# TPadTabletBattery.net
KiCad netlist of a schematic drawn in EAGLE
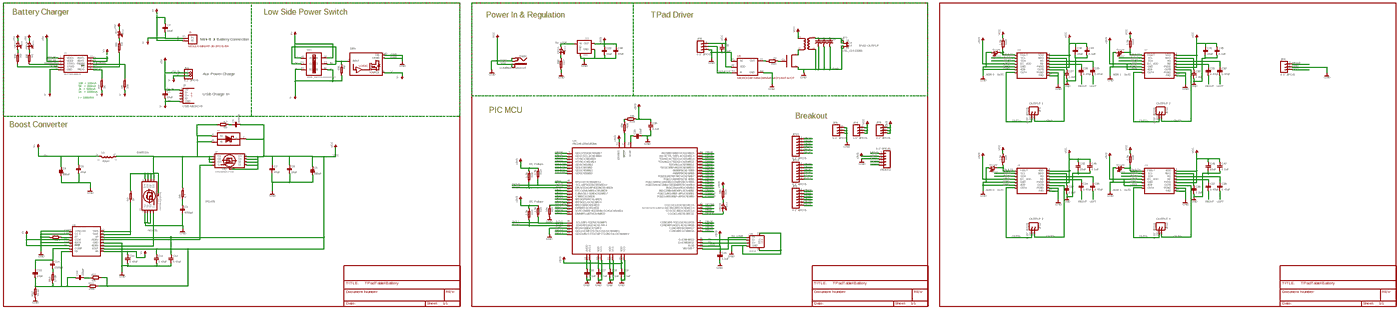
[diagram p0: schematic, sheet 1, overview]
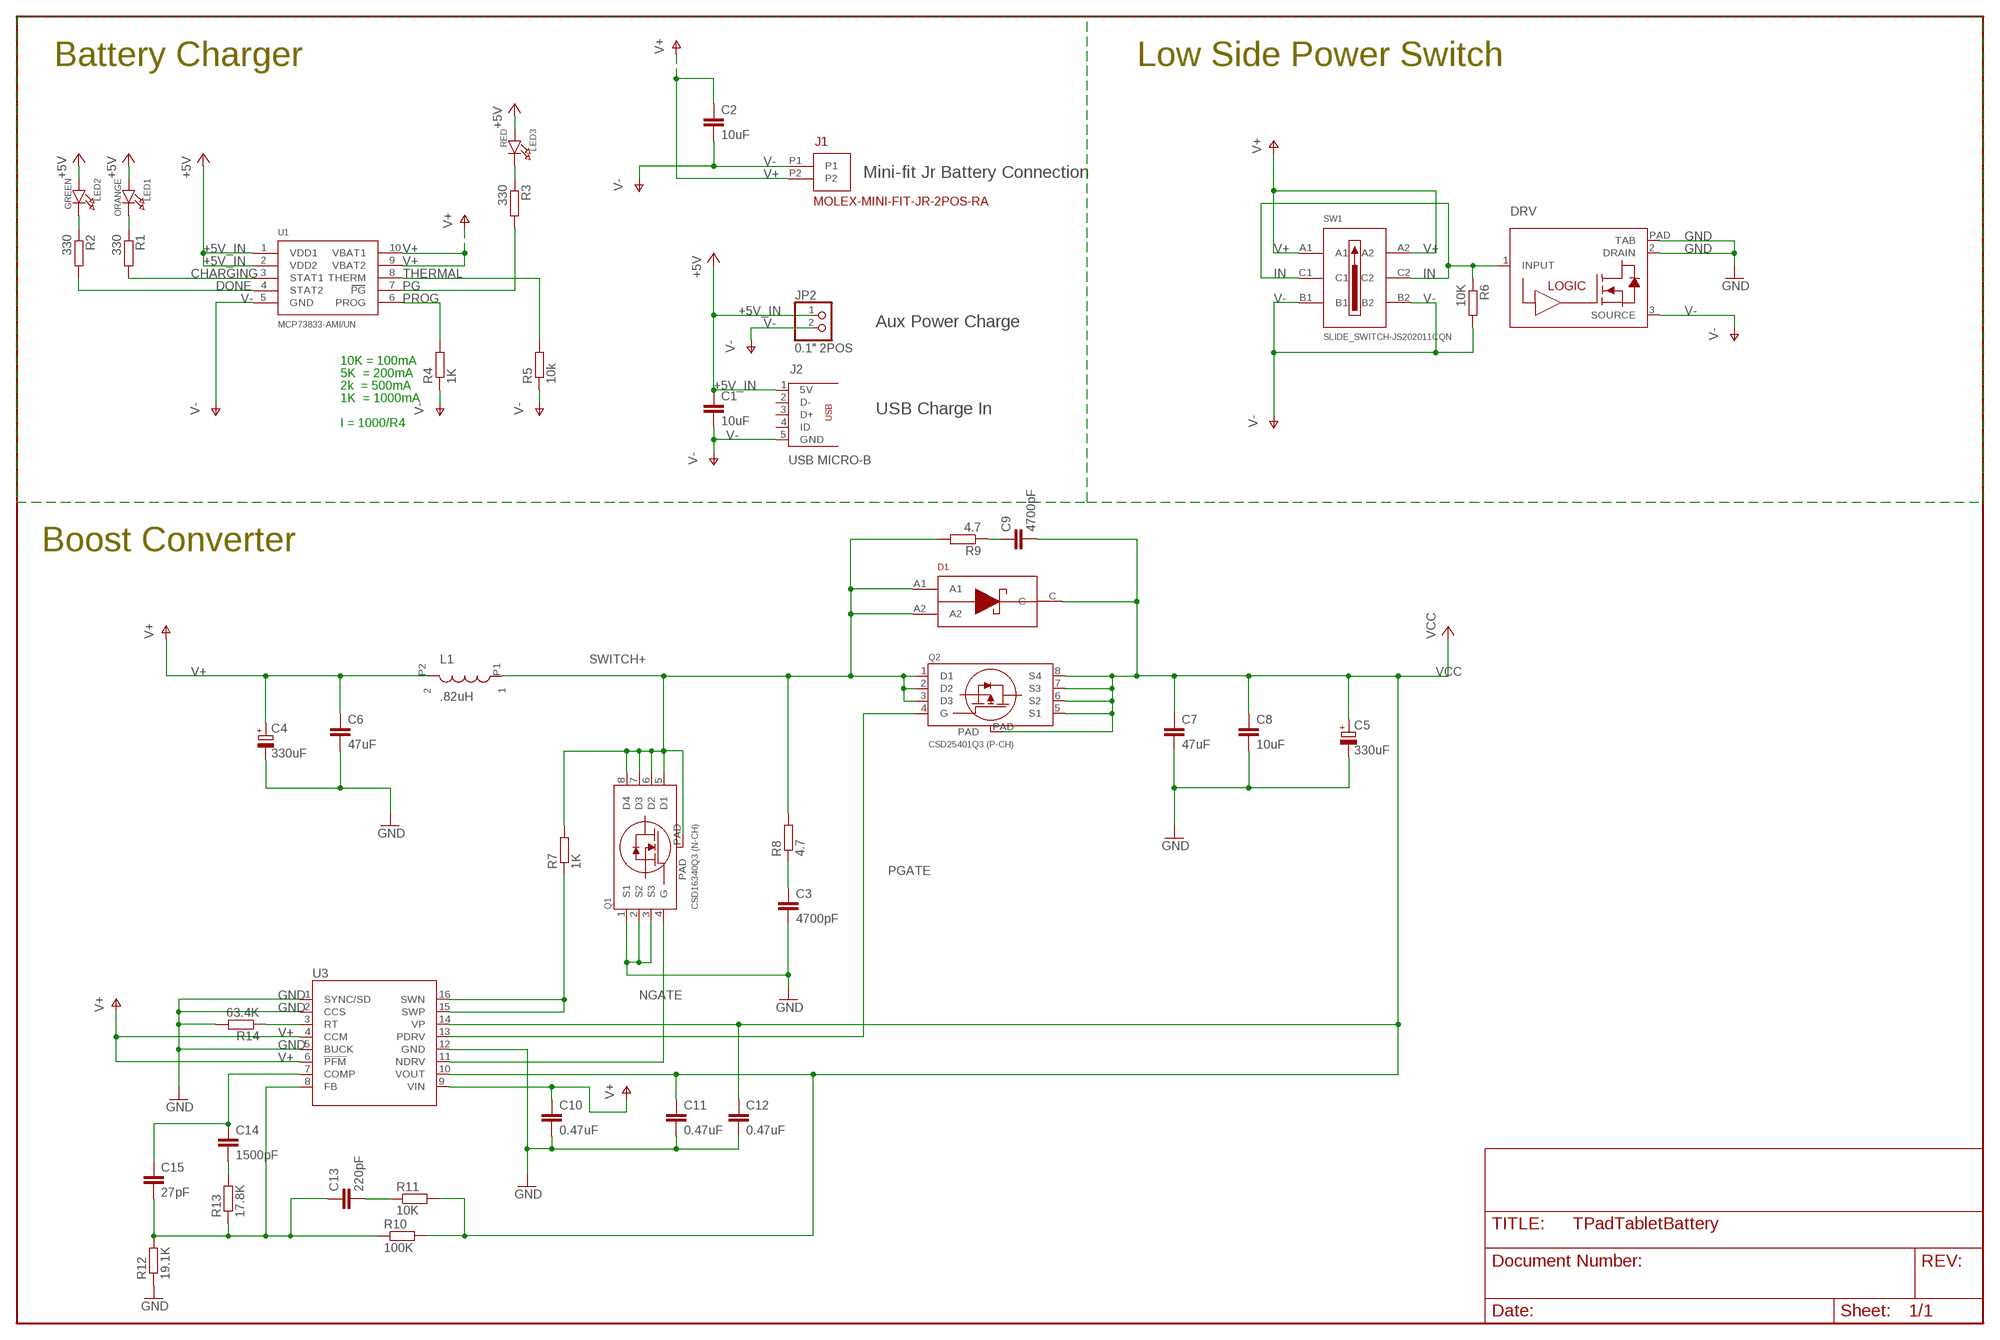
[diagram p1: schematic, sheet 1, part 1 of 4]
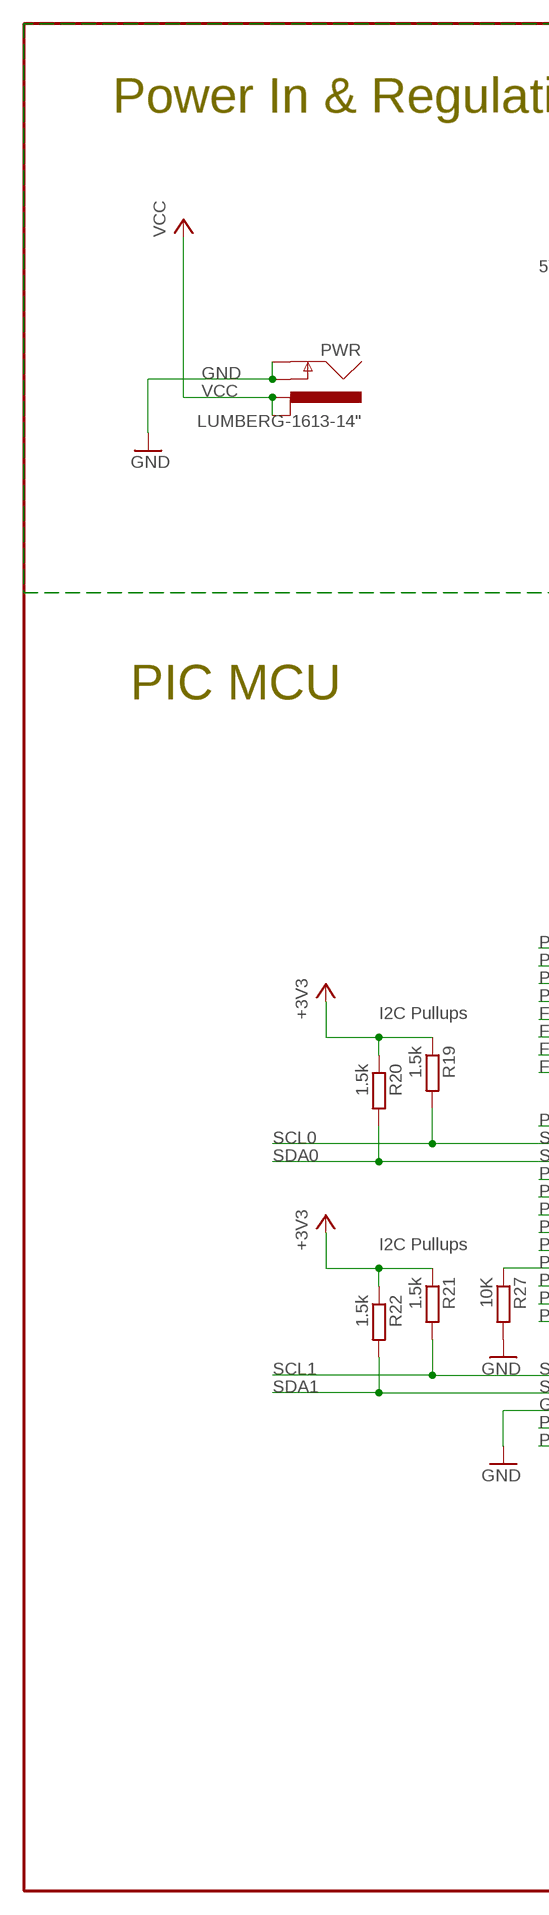
[diagram p2: schematic, sheet 1, part 2 of 4]
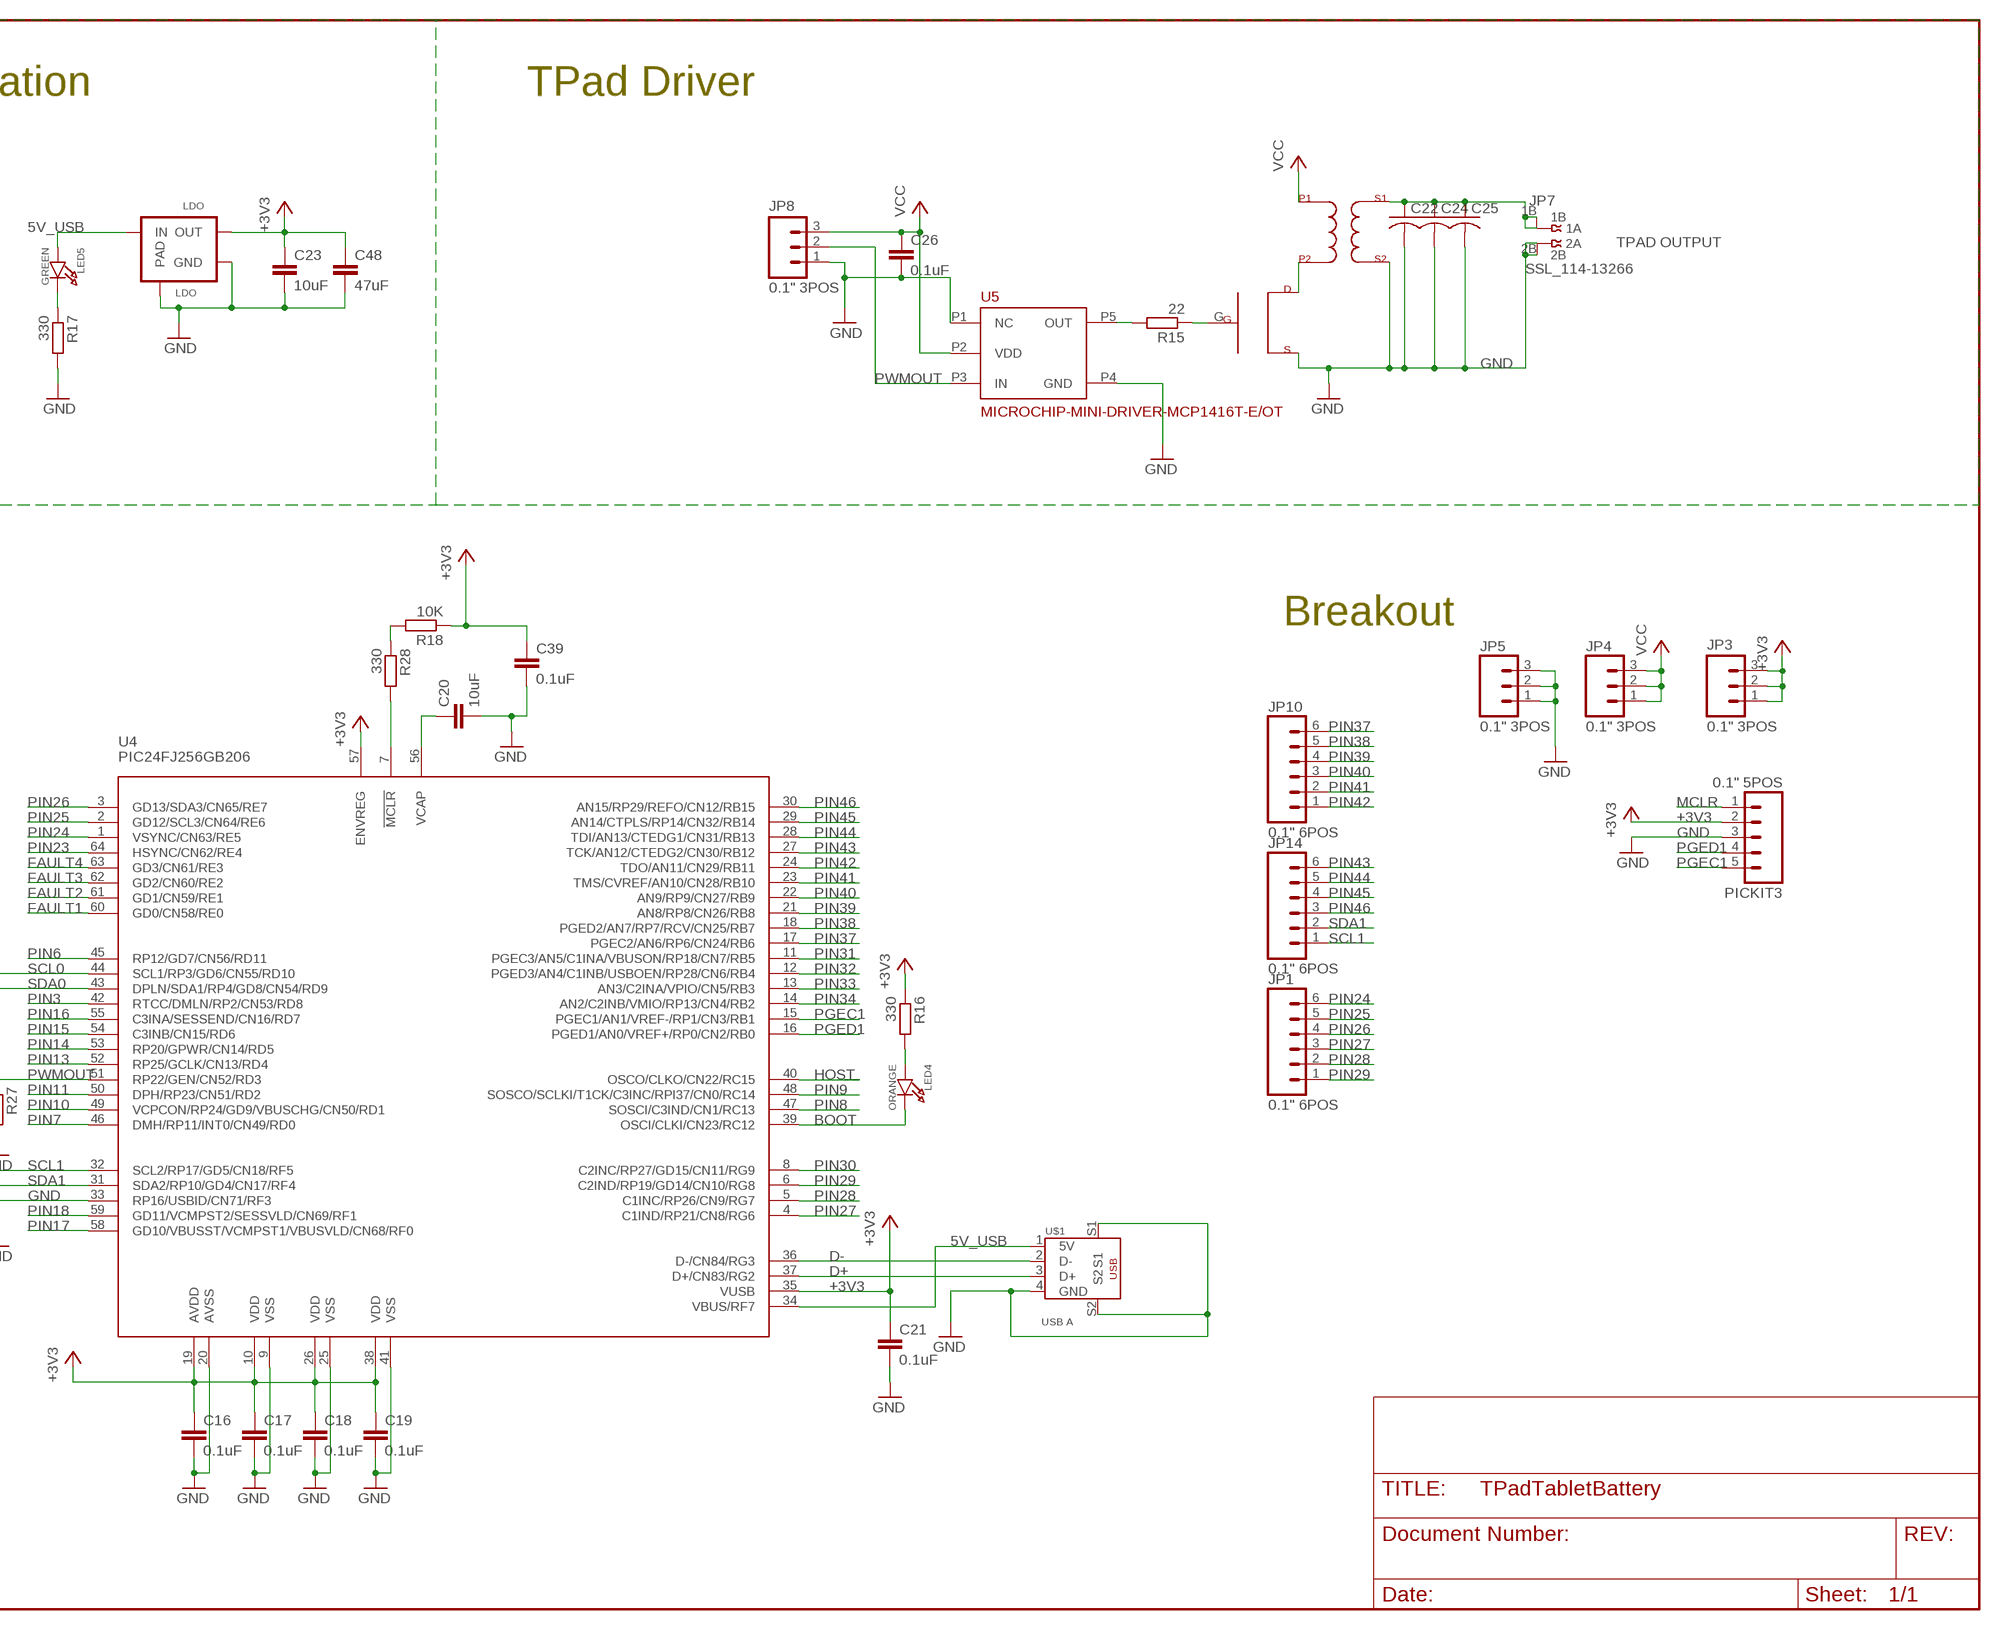
[diagram p3: schematic, sheet 1, part 3 of 4]
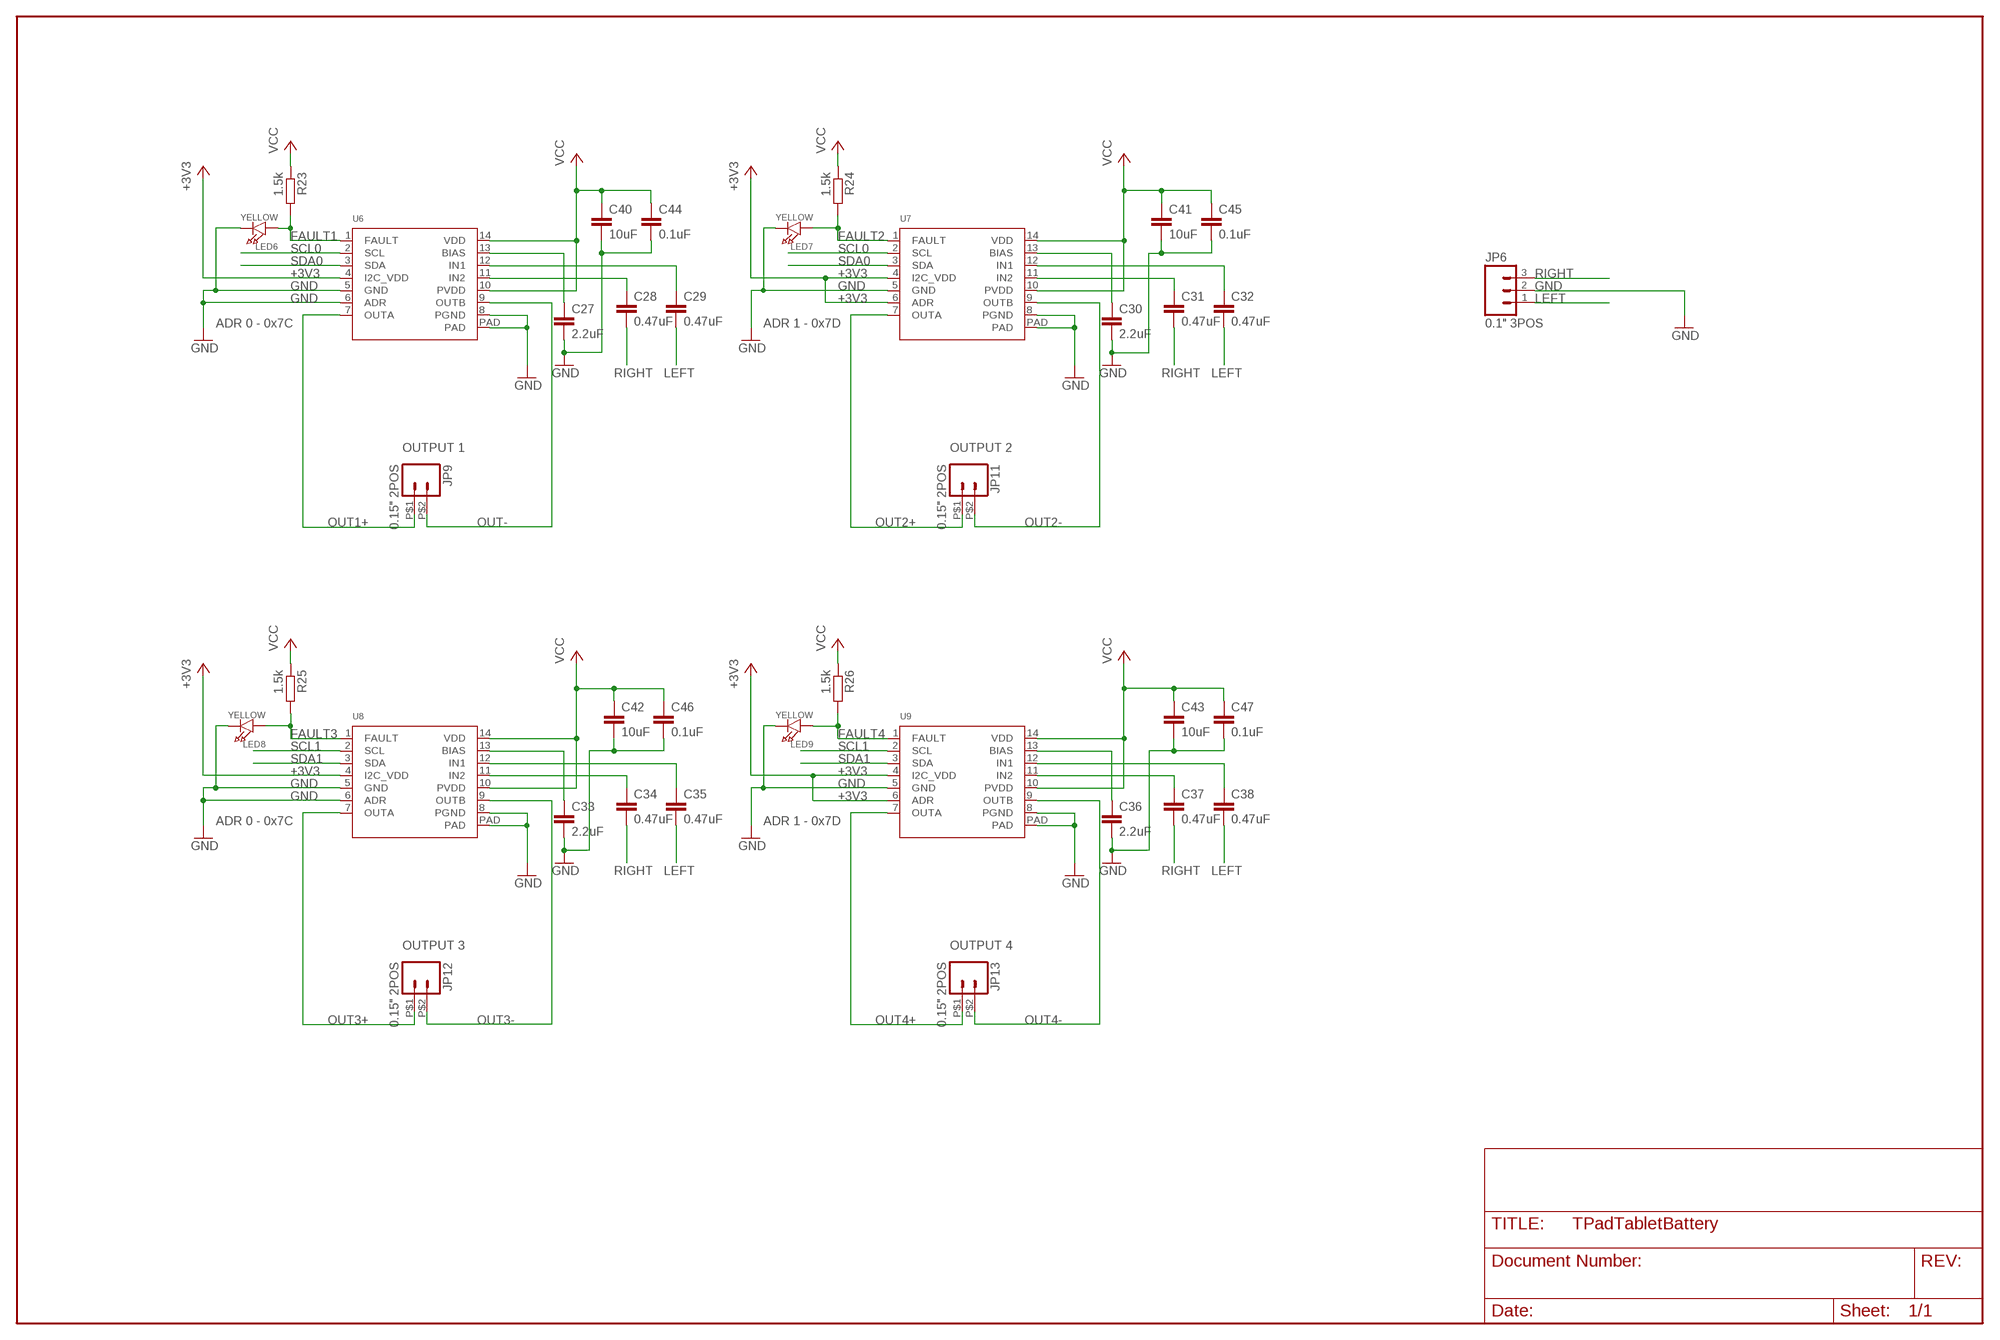
[diagram p4: schematic, sheet 1, part 4 of 4]

(export (version "E")
  (design (tool "Eeschema 10.0.6"))
  (components
    (comp (ref "C1")
      (value "10uF")
      (footprint "eagle-import:C0805")
      (libsource (lib "eagle-import") (part "C-EUC0805"))
    )
    (comp (ref "C2")
      (value "10uF")
      (footprint "eagle-import:C0805")
      (libsource (lib "eagle-import") (part "C-EUC0805"))
    )
    (comp (ref "C3")
      (value "4700pF")
      (footprint "eagle-import:C0603")
      (libsource (lib "eagle-import") (part "C-EUC0603"))
    )
    (comp (ref "C4")
      (value "330uF")
      (footprint "eagle-import:C_6032-28R")
      (libsource (lib "eagle-import") (part "CPOL-EUC/6032-28R"))
    )
    (comp (ref "C5")
      (value "330uF")
      (footprint "eagle-import:C_6032-28R")
      (libsource (lib "eagle-import") (part "CPOL-EUC/6032-28R"))
    )
    (comp (ref "C6")
      (value "47uF")
      (footprint "eagle-import:C1210")
      (libsource (lib "eagle-import") (part "C-EUC1210"))
    )
    (comp (ref "C7")
      (value "47uF")
      (footprint "eagle-import:C1210")
      (libsource (lib "eagle-import") (part "C-EUC1210"))
    )
    (comp (ref "C8")
      (value "10uF")
      (footprint "eagle-import:C0805")
      (libsource (lib "eagle-import") (part "C-EUC0805"))
    )
    (comp (ref "C9")
      (value "4700pF")
      (footprint "eagle-import:C0603")
      (libsource (lib "eagle-import") (part "C-EUC0603"))
    )
    (comp (ref "C10")
      (value "0.47uF")
      (footprint "eagle-import:C0603")
      (libsource (lib "eagle-import") (part "C-EUC0603"))
    )
    (comp (ref "C11")
      (value "0.47uF")
      (footprint "eagle-import:C0603")
      (libsource (lib "eagle-import") (part "C-EUC0603"))
    )
    (comp (ref "C12")
      (value "0.47uF")
      (footprint "eagle-import:C0603")
      (libsource (lib "eagle-import") (part "C-EUC0603"))
    )
    (comp (ref "C13")
      (value "220pF")
      (footprint "eagle-import:C0603")
      (libsource (lib "eagle-import") (part "C-EUC0603"))
    )
    (comp (ref "C14")
      (value "1500pF")
      (footprint "eagle-import:C0603")
      (libsource (lib "eagle-import") (part "C-EUC0603"))
    )
    (comp (ref "C15")
      (value "27pF")
      (footprint "eagle-import:C0603")
      (libsource (lib "eagle-import") (part "C-EUC0603"))
    )
    (comp (ref "C16")
      (value "0.1uF")
      (footprint "eagle-import:C0603")
      (libsource (lib "eagle-import") (part "C-EUC0603"))
    )
    (comp (ref "C17")
      (value "0.1uF")
      (footprint "eagle-import:C0603")
      (libsource (lib "eagle-import") (part "C-EUC0603"))
    )
    (comp (ref "C18")
      (value "0.1uF")
      (footprint "eagle-import:C0603")
      (libsource (lib "eagle-import") (part "C-EUC0603"))
    )
    (comp (ref "C19")
      (value "0.1uF")
      (footprint "eagle-import:C0603")
      (libsource (lib "eagle-import") (part "C-EUC0603"))
    )
    (comp (ref "C20")
      (value "10uF")
      (footprint "eagle-import:C0805")
      (libsource (lib "eagle-import") (part "C-EUC0805"))
    )
    (comp (ref "C21")
      (value "0.1uF")
      (footprint "eagle-import:C0603")
      (libsource (lib "eagle-import") (part "C-EUC0603"))
    )
    (comp (ref "C22")
      (value "C-US050-035X075")
      (footprint "eagle-import:C050-035X075")
      (libsource (lib "eagle-import") (part "C-US050-035X075"))
    )
    (comp (ref "C23")
      (value "10uF")
      (footprint "eagle-import:C0805")
      (libsource (lib "eagle-import") (part "C-EUC0805"))
    )
    (comp (ref "C24")
      (value "C-US050-035X075")
      (footprint "eagle-import:C050-035X075")
      (libsource (lib "eagle-import") (part "C-US050-035X075"))
    )
    (comp (ref "C25")
      (value "C-US050-035X075")
      (footprint "eagle-import:C050-035X075")
      (libsource (lib "eagle-import") (part "C-US050-035X075"))
    )
    (comp (ref "C26")
      (value "0.1uF")
      (footprint "eagle-import:C0603")
      (libsource (lib "eagle-import") (part "C-EUC0603"))
    )
    (comp (ref "C27")
      (value "2.2uF")
      (footprint "eagle-import:C0603")
      (libsource (lib "eagle-import") (part "C-EUC0603"))
    )
    (comp (ref "C28")
      (value "0.47uF")
      (footprint "eagle-import:C0603")
      (libsource (lib "eagle-import") (part "C-EUC0603"))
    )
    (comp (ref "C29")
      (value "0.47uF")
      (footprint "eagle-import:C0603")
      (libsource (lib "eagle-import") (part "C-EUC0603"))
    )
    (comp (ref "C30")
      (value "2.2uF")
      (footprint "eagle-import:C0603")
      (libsource (lib "eagle-import") (part "C-EUC0603"))
    )
    (comp (ref "C31")
      (value "0.47uF")
      (footprint "eagle-import:C0603")
      (libsource (lib "eagle-import") (part "C-EUC0603"))
    )
    (comp (ref "C32")
      (value "0.47uF")
      (footprint "eagle-import:C0603")
      (libsource (lib "eagle-import") (part "C-EUC0603"))
    )
    (comp (ref "C33")
      (value "2.2uF")
      (footprint "eagle-import:C0603")
      (libsource (lib "eagle-import") (part "C-EUC0603"))
    )
    (comp (ref "C34")
      (value "0.47uF")
      (footprint "eagle-import:C0603")
      (libsource (lib "eagle-import") (part "C-EUC0603"))
    )
    (comp (ref "C35")
      (value "0.47uF")
      (footprint "eagle-import:C0603")
      (libsource (lib "eagle-import") (part "C-EUC0603"))
    )
    (comp (ref "C36")
      (value "2.2uF")
      (footprint "eagle-import:C0603")
      (libsource (lib "eagle-import") (part "C-EUC0603"))
    )
    (comp (ref "C37")
      (value "0.47uF")
      (footprint "eagle-import:C0603")
      (libsource (lib "eagle-import") (part "C-EUC0603"))
    )
    (comp (ref "C38")
      (value "0.47uF")
      (footprint "eagle-import:C0603")
      (libsource (lib "eagle-import") (part "C-EUC0603"))
    )
    (comp (ref "C39")
      (value "0.1uF")
      (footprint "eagle-import:C0603")
      (libsource (lib "eagle-import") (part "C-EUC0603"))
    )
    (comp (ref "C40")
      (value "10uF")
      (footprint "eagle-import:C0805")
      (libsource (lib "eagle-import") (part "C-EUC0805"))
    )
    (comp (ref "C41")
      (value "10uF")
      (footprint "eagle-import:C0805")
      (libsource (lib "eagle-import") (part "C-EUC0805"))
    )
    (comp (ref "C42")
      (value "10uF")
      (footprint "eagle-import:C0805")
      (libsource (lib "eagle-import") (part "C-EUC0805"))
    )
    (comp (ref "C43")
      (value "10uF")
      (footprint "eagle-import:C0805")
      (libsource (lib "eagle-import") (part "C-EUC0805"))
    )
    (comp (ref "C44")
      (value "0.1uF")
      (footprint "eagle-import:C0603")
      (libsource (lib "eagle-import") (part "C-EUC0603"))
    )
    (comp (ref "C45")
      (value "0.1uF")
      (footprint "eagle-import:C0603")
      (libsource (lib "eagle-import") (part "C-EUC0603"))
    )
    (comp (ref "C46")
      (value "0.1uF")
      (footprint "eagle-import:C0603")
      (libsource (lib "eagle-import") (part "C-EUC0603"))
    )
    (comp (ref "C47")
      (value "0.1uF")
      (footprint "eagle-import:C0603")
      (libsource (lib "eagle-import") (part "C-EUC0603"))
    )
    (comp (ref "C48")
      (value "47uF")
      (footprint "eagle-import:C1210")
      (libsource (lib "eagle-import") (part "C-EUC1210"))
    )
    (comp (ref "D1")
      (value "POWER-DIODE_PDS835L")
      (footprint "eagle-import:POWER-DIODE_PDS835L")
      (libsource (lib "eagle-import") (part "POWER-DIODE_PDS835L"))
    )
    (comp (ref "DRV")
      (value "VLN5050")
      (footprint "eagle-import:SOT-223")
      (libsource (lib "eagle-import") (part "VLN5050"))
    )
    (comp (ref "J1")
      (value "MOLEX-MINI-FIT-JR-2POS-RA")
      (footprint "eagle-import:MOLEX-MINI-FIT-JR-2POS-RA")
      (libsource (lib "eagle-import") (part "MOLEX-MINI-FIT-JR-2POS-RA"))
    )
    (comp (ref "J2")
      (value "USB MICRO-B")
      (footprint "eagle-import:USB-MICROB_SMD")
      (libsource (lib "eagle-import") (part "USB_MICROMICRO-BAMPHENOL_10118193-0001LF"))
    )
    (comp (ref "JP1")
      (value "0.1\" 6POS")
      (footprint "eagle-import:1X06")
      (libsource (lib "eagle-import") (part "M06SIP"))
    )
    (comp (ref "JP2")
      (value "0.1\" 2POS")
      (footprint "eagle-import:MICROBUILDER_1X02_ROUND")
      (libsource (lib "eagle-import") (part "MICROBUILDER_HEADER-1X2ROUND"))
    )
    (comp (ref "JP3")
      (value "0.1\" 3POS")
      (footprint "eagle-import:1X03")
      (libsource (lib "eagle-import") (part "M03PTH"))
    )
    (comp (ref "JP4")
      (value "0.1\" 3POS")
      (footprint "eagle-import:1X03")
      (libsource (lib "eagle-import") (part "M03PTH"))
    )
    (comp (ref "JP5")
      (value "0.1\" 3POS")
      (footprint "eagle-import:1X03")
      (libsource (lib "eagle-import") (part "M03PTH"))
    )
    (comp (ref "JP6")
      (value "0.1\" 3POS")
      (footprint "eagle-import:1X03")
      (libsource (lib "eagle-import") (part "M03PTH"))
    )
    (comp (ref "JP7")
      (value "SSL_114-13266")
      (footprint "eagle-import:SSL_114-13266")
      (libsource (lib "eagle-import") (part "SSL_114-13266"))
    )
    (comp (ref "JP8")
      (value "0.1\" 3POS")
      (footprint "eagle-import:1X03")
      (libsource (lib "eagle-import") (part "M03PTH"))
    )
    (comp (ref "JP9")
      (value "0.15\" 2POS")
      (footprint "eagle-import:1X02_BIG")
      (libsource (lib "eagle-import") (part "M02PTH2"))
    )
    (comp (ref "JP10")
      (value "0.1\" 6POS")
      (footprint "eagle-import:1X06")
      (libsource (lib "eagle-import") (part "M06SIP"))
    )
    (comp (ref "JP11")
      (value "0.15\" 2POS")
      (footprint "eagle-import:1X02_BIG")
      (libsource (lib "eagle-import") (part "M02PTH2"))
    )
    (comp (ref "JP12")
      (value "0.15\" 2POS")
      (footprint "eagle-import:1X02_BIG")
      (libsource (lib "eagle-import") (part "M02PTH2"))
    )
    (comp (ref "JP13")
      (value "0.15\" 2POS")
      (footprint "eagle-import:1X02_BIG")
      (libsource (lib "eagle-import") (part "M02PTH2"))
    )
    (comp (ref "JP14")
      (value "0.1\" 6POS")
      (footprint "eagle-import:1X06")
      (libsource (lib "eagle-import") (part "M06SIP"))
    )
    (comp (ref "L1")
      (value ".82uH")
      (footprint "eagle-import:.82UH_INDUCTOR-IHLP3232DZERR82M01")
      (libsource (lib "eagle-import") (part ".82UH_INDUCTOR-IHLP3232DZERR82M01"))
    )
    (comp (ref "LDO")
      (value "LDO")
      (footprint "eagle-import:SOT-223")
      (libsource (lib "eagle-import") (part "LDO"))
    )
    (comp (ref "LED1")
      (value "ORANGE")
      (footprint "eagle-import:MICROBUILDER_CHIPLED_0603")
      (libsource (lib "eagle-import") (part "MICROBUILDER_LED0603"))
    )
    (comp (ref "LED2")
      (value "GREEN")
      (footprint "eagle-import:MICROBUILDER_CHIPLED_0603")
      (libsource (lib "eagle-import") (part "MICROBUILDER_LED0603"))
    )
    (comp (ref "LED3")
      (value "RED")
      (footprint "eagle-import:MICROBUILDER_CHIPLED_0603")
      (libsource (lib "eagle-import") (part "MICROBUILDER_LED0603"))
    )
    (comp (ref "LED4")
      (value "ORANGE")
      (footprint "eagle-import:MICROBUILDER_CHIPLED_0603")
      (libsource (lib "eagle-import") (part "MICROBUILDER_LED0603"))
    )
    (comp (ref "LED5")
      (value "GREEN")
      (footprint "eagle-import:MICROBUILDER_CHIPLED_0603")
      (libsource (lib "eagle-import") (part "MICROBUILDER_LED0603"))
    )
    (comp (ref "LED6")
      (value "YELLOW")
      (footprint "eagle-import:MICROBUILDER_CHIPLED_0603")
      (libsource (lib "eagle-import") (part "MICROBUILDER_LED0603"))
    )
    (comp (ref "LED7")
      (value "YELLOW")
      (footprint "eagle-import:MICROBUILDER_CHIPLED_0603")
      (libsource (lib "eagle-import") (part "MICROBUILDER_LED0603"))
    )
    (comp (ref "LED8")
      (value "YELLOW")
      (footprint "eagle-import:MICROBUILDER_CHIPLED_0603")
      (libsource (lib "eagle-import") (part "MICROBUILDER_LED0603"))
    )
    (comp (ref "LED9")
      (value "YELLOW")
      (footprint "eagle-import:MICROBUILDER_CHIPLED_0603")
      (libsource (lib "eagle-import") (part "MICROBUILDER_LED0603"))
    )
    (comp (ref "PICKIT3")
      (value "0.1\" 5POS")
      (footprint "eagle-import:1X05")
      (libsource (lib "eagle-import") (part "M05PTH"))
    )
    (comp (ref "PWR")
      (value "LUMBERG-1613-14\"")
      (footprint "eagle-import:LUMBERG-1613_14")
      (libsource (lib "eagle-import") (part "LUMBERG-1613-14{dblquote}"))
    )
    (comp (ref "Q1")
      (value "CSD16340Q3")
      (footprint "eagle-import:CSDXXXXQ3")
      (libsource (lib "eagle-import") (part "CSD16340Q3"))
    )
    (comp (ref "Q2")
      (value "CSD25401Q3")
      (footprint "eagle-import:CSDXXXXQ3")
      (libsource (lib "eagle-import") (part "CSD25401Q3"))
    )
    (comp (ref "Q3")
      (value "STP27N3LH5")
      (footprint "eagle-import:TPAD_TO220")
      (libsource (lib "eagle-import") (part "TPAD_IRF520N"))
    )
    (comp (ref "R1")
      (value "330")
      (footprint "eagle-import:R0603")
      (libsource (lib "eagle-import") (part "R-EU_R0603"))
    )
    (comp (ref "R2")
      (value "330")
      (footprint "eagle-import:R0603")
      (libsource (lib "eagle-import") (part "R-EU_R0603"))
    )
    (comp (ref "R3")
      (value "330")
      (footprint "eagle-import:R0603")
      (libsource (lib "eagle-import") (part "R-EU_R0603"))
    )
    (comp (ref "R4")
      (value "1K")
      (footprint "eagle-import:R0805")
      (libsource (lib "eagle-import") (part "R-EU_R0805"))
    )
    (comp (ref "R5")
      (value "10k")
      (footprint "eagle-import:R0805")
      (libsource (lib "eagle-import") (part "R-EU_R0805"))
    )
    (comp (ref "R6")
      (value "10K")
      (footprint "eagle-import:R0603")
      (libsource (lib "eagle-import") (part "R-EU_R0603"))
    )
    (comp (ref "R7")
      (value "1K")
      (footprint "eagle-import:R0603")
      (libsource (lib "eagle-import") (part "R-EU_R0603"))
    )
    (comp (ref "R8")
      (value "4.7")
      (footprint "eagle-import:R0603")
      (libsource (lib "eagle-import") (part "R-EU_R0603"))
    )
    (comp (ref "R9")
      (value "4.7")
      (footprint "eagle-import:R0603")
      (libsource (lib "eagle-import") (part "R-EU_R0603"))
    )
    (comp (ref "R10")
      (value "100K")
      (footprint "eagle-import:R0603")
      (libsource (lib "eagle-import") (part "R-EU_R0603"))
    )
    (comp (ref "R11")
      (value "10K")
      (footprint "eagle-import:R0603")
      (libsource (lib "eagle-import") (part "R-EU_R0603"))
    )
    (comp (ref "R12")
      (value "19.1K")
      (footprint "eagle-import:R0603")
      (libsource (lib "eagle-import") (part "R-EU_R0603"))
    )
    (comp (ref "R13")
      (value "17.8K")
      (footprint "eagle-import:R0603")
      (libsource (lib "eagle-import") (part "R-EU_R0603"))
    )
    (comp (ref "R14")
      (value "63.4K")
      (footprint "eagle-import:R0603")
      (libsource (lib "eagle-import") (part "R-EU_R0603"))
    )
    (comp (ref "R15")
      (value "22")
      (footprint "eagle-import:R0603")
      (libsource (lib "eagle-import") (part "R-EU_R0603"))
    )
    (comp (ref "R16")
      (value "330")
      (footprint "eagle-import:R0603")
      (libsource (lib "eagle-import") (part "R-EU_R0603"))
    )
    (comp (ref "R17")
      (value "330")
      (footprint "eagle-import:R0603")
      (libsource (lib "eagle-import") (part "R-EU_R0603"))
    )
    (comp (ref "R18")
      (value "10K")
      (footprint "eagle-import:R0603")
      (libsource (lib "eagle-import") (part "R-EU_R0603"))
    )
    (comp (ref "R19")
      (value "1.5k")
      (footprint "eagle-import:R0603")
      (libsource (lib "eagle-import") (part "R-EU_R0603"))
    )
    (comp (ref "R20")
      (value "1.5k")
      (footprint "eagle-import:R0603")
      (libsource (lib "eagle-import") (part "R-EU_R0603"))
    )
    (comp (ref "R21")
      (value "1.5k")
      (footprint "eagle-import:R0603")
      (libsource (lib "eagle-import") (part "R-EU_R0603"))
    )
    (comp (ref "R22")
      (value "1.5k")
      (footprint "eagle-import:R0603")
      (libsource (lib "eagle-import") (part "R-EU_R0603"))
    )
    (comp (ref "R23")
      (value "1.5k")
      (footprint "eagle-import:R0603")
      (libsource (lib "eagle-import") (part "R-EU_R0603"))
    )
    (comp (ref "R24")
      (value "1.5k")
      (footprint "eagle-import:R0603")
      (libsource (lib "eagle-import") (part "R-EU_R0603"))
    )
    (comp (ref "R25")
      (value "1.5k")
      (footprint "eagle-import:R0603")
      (libsource (lib "eagle-import") (part "R-EU_R0603"))
    )
    (comp (ref "R26")
      (value "1.5k")
      (footprint "eagle-import:R0603")
      (libsource (lib "eagle-import") (part "R-EU_R0603"))
    )
    (comp (ref "R27")
      (value "10K")
      (footprint "eagle-import:R0603")
      (libsource (lib "eagle-import") (part "R-EU_R0603"))
    )
    (comp (ref "R28")
      (value "330")
      (footprint "eagle-import:R0603")
      (libsource (lib "eagle-import") (part "R-EU_R0603"))
    )
    (comp (ref "SW1")
      (value "SLIDE_SWITCH-JS202011CQN")
      (footprint "eagle-import:SLIDE_SWITCH-JS202011CQN")
      (libsource (lib "eagle-import") (part "SLIDE_SWITCH-JS202011CQN"))
    )
    (comp (ref "U$1")
      (value "USB A")
      (footprint "eagle-import:USB-A_SOCKET-THT")
      (libsource (lib "eagle-import") (part "USBSOCKET-THT"))
    )
    (comp (ref "U$4")
      (value "TRANSFORMER")
      (footprint "eagle-import:TRANSFORMER")
      (libsource (lib "eagle-import") (part "TRANSFORMER"))
    )
    (comp (ref "U1")
      (value "MCP73833-AMI/UN")
      (footprint "eagle-import:MICROBUILDER_MSOP10")
      (libsource (lib "eagle-import") (part "MICROBUILDER_MCP73833"))
    )
    (comp (ref "U3")
      (value "TPS43000")
      (footprint "eagle-import:TSSOP16")
      (libsource (lib "eagle-import") (part "TPS43000"))
    )
    (comp (ref "U4")
      (value "PIC24FJ256GB206")
      (footprint "eagle-import:PIC24FXXX_TQFP64")
      (libsource (lib "eagle-import") (part "PIC24FXXXDAX06"))
    )
    (comp (ref "U5")
      (value "MICROCHIP-MINI-DRIVER-MCP1416T-E/OT")
      (footprint "eagle-import:MICROCHIP-MINI-DRIVER-MCP1416T-E_OT")
      (libsource (lib "eagle-import") (part "MICROCHIP-MINI-DRIVER-MCP1416T-E/OT"))
    )
    (comp (ref "U6")
      (value "LM48100Q")
      (footprint "eagle-import:LM48100")
      (libsource (lib "eagle-import") (part "LM48100Q"))
    )
    (comp (ref "U7")
      (value "LM48100Q")
      (footprint "eagle-import:LM48100")
      (libsource (lib "eagle-import") (part "LM48100Q"))
    )
    (comp (ref "U8")
      (value "LM48100Q")
      (footprint "eagle-import:LM48100")
      (libsource (lib "eagle-import") (part "LM48100Q"))
    )
    (comp (ref "U9")
      (value "LM48100Q")
      (footprint "eagle-import:LM48100")
      (libsource (lib "eagle-import") (part "LM48100Q"))
    )
  )
  (nets
    (net (code "1") (name "+3V3") (class "Default")
      (node (ref "C16") (pin "1") (pinfunction "1_1") (pintype "passive"))
      (node (ref "C17") (pin "1") (pinfunction "1_1") (pintype "passive"))
      (node (ref "C18") (pin "1") (pinfunction "1_1") (pintype "passive"))
      (node (ref "C19") (pin "1") (pinfunction "1_1") (pintype "passive"))
      (node (ref "C21") (pin "1") (pinfunction "1_1") (pintype "passive"))
      (node (ref "C23") (pin "1") (pinfunction "1_1") (pintype "passive"))
      (node (ref "C39") (pin "1") (pinfunction "1_1") (pintype "passive"))
      (node (ref "C48") (pin "1") (pinfunction "1_1") (pintype "passive"))
      (node (ref "JP3") (pin "1") (pinfunction "1_1") (pintype "passive"))
      (node (ref "JP3") (pin "2") (pinfunction "2_2") (pintype "passive"))
      (node (ref "JP3") (pin "3") (pinfunction "3_3") (pintype "passive"))
      (node (ref "LDO") (pin "3") (pinfunction "OUT_3") (pintype "passive"))
      (node (ref "PICKIT3") (pin "2") (pinfunction "2_2") (pintype "passive"))
      (node (ref "R16") (pin "1") (pinfunction "1_1") (pintype "passive"))
      (node (ref "R18") (pin "1") (pinfunction "1_1") (pintype "passive"))
      (node (ref "R19") (pin "1") (pinfunction "1_1") (pintype "passive"))
      (node (ref "R20") (pin "1") (pinfunction "1_1") (pintype "passive"))
      (node (ref "R21") (pin "1") (pinfunction "1_1") (pintype "passive"))
      (node (ref "R22") (pin "1") (pinfunction "1_1") (pintype "passive"))
      (node (ref "U4") (pin "10") (pinfunction "VDD_10") (pintype "power_in"))
      (node (ref "U4") (pin "19") (pinfunction "AVDD_19") (pintype "power_in"))
      (node (ref "U4") (pin "26") (pinfunction "VDD_26") (pintype "power_in"))
      (node (ref "U4") (pin "35") (pinfunction "VUSB_35") (pintype "power_in"))
      (node (ref "U4") (pin "38") (pinfunction "VDD_38") (pintype "power_in"))
      (node (ref "U4") (pin "57") (pinfunction "ENVREG_57") (pintype "input"))
      (node (ref "U6") (pin "4") (pinfunction "I2C_VDD_4") (pintype "bidirectional"))
      (node (ref "U7") (pin "4") (pinfunction "I2C_VDD_4") (pintype "bidirectional"))
      (node (ref "U7") (pin "6") (pinfunction "ADR_6") (pintype "bidirectional"))
      (node (ref "U8") (pin "4") (pinfunction "I2C_VDD_4") (pintype "bidirectional"))
      (node (ref "U9") (pin "4") (pinfunction "I2C_VDD_4") (pintype "bidirectional"))
      (node (ref "U9") (pin "6") (pinfunction "ADR_6") (pintype "bidirectional"))
    )
    (net (code "2") (name "+5V") (class "Default")
      (node (ref "C1") (pin "1") (pinfunction "1_1") (pintype "passive"))
      (node (ref "J2") (pin "1") (pinfunction "5V_1") (pintype "bidirectional"))
      (node (ref "JP2") (pin "1") (pinfunction "1_1") (pintype "passive"))
      (node (ref "LED1") (pin "A") (pinfunction "A_A") (pintype "passive"))
      (node (ref "LED2") (pin "A") (pinfunction "A_A") (pintype "passive"))
      (node (ref "LED3") (pin "A") (pinfunction "A_A") (pintype "passive"))
      (node (ref "U1") (pin "1") (pinfunction "VDD1_1") (pintype "bidirectional"))
      (node (ref "U1") (pin "2") (pinfunction "VDD2_2") (pintype "bidirectional"))
    )
    (net (code "3") (name "/5V_USB") (class "Default")
      (node (ref "LDO") (pin "1") (pinfunction "IN_1") (pintype "input"))
      (node (ref "LED5") (pin "A") (pinfunction "A_A") (pintype "passive"))
      (node (ref "U$1") (pin "1") (pinfunction "5V_1") (pintype "bidirectional"))
      (node (ref "U4") (pin "34") (pinfunction "VBUS/RF7_34") (pintype "input"))
    )
    (net (code "4") (name "/BOOT") (class "Default")
      (node (ref "LED4") (pin "C") (pinfunction "C_C") (pintype "passive"))
      (node (ref "U4") (pin "39") (pinfunction "OSCI/CLKI/CN23/RC12_39") (pintype "bidirectional"))
    )
    (net (code "5") (name "/CHARGING") (class "Default")
      (node (ref "R1") (pin "2") (pinfunction "2_2") (pintype "passive"))
      (node (ref "U1") (pin "3") (pinfunction "STAT1_3") (pintype "bidirectional"))
    )
    (net (code "6") (name "/D+") (class "Default")
      (node (ref "U$1") (pin "3") (pinfunction "D+_3") (pintype "bidirectional"))
      (node (ref "U4") (pin "37") (pinfunction "D+/CN83/RG2_37") (pintype "bidirectional"))
    )
    (net (code "7") (name "/D-") (class "Default")
      (node (ref "U$1") (pin "2") (pinfunction "D-_2") (pintype "bidirectional"))
      (node (ref "U4") (pin "36") (pinfunction "D-/CN84/RG3_36") (pintype "bidirectional"))
    )
    (net (code "8") (name "/DONE") (class "Default")
      (node (ref "R2") (pin "2") (pinfunction "2_2") (pintype "passive"))
      (node (ref "U1") (pin "4") (pinfunction "STAT2_4") (pintype "bidirectional"))
    )
    (net (code "9") (name "/FAULT1") (class "Default")
      (node (ref "LED6") (pin "A") (pinfunction "A_A") (pintype "passive"))
      (node (ref "R23") (pin "2") (pinfunction "2_2") (pintype "passive"))
      (node (ref "U4") (pin "60") (pinfunction "GD0/CN58/RE0_60") (pintype "bidirectional"))
      (node (ref "U6") (pin "1") (pinfunction "FAULT_1") (pintype "bidirectional"))
    )
    (net (code "10") (name "/FAULT2") (class "Default")
      (node (ref "LED7") (pin "A") (pinfunction "A_A") (pintype "passive"))
      (node (ref "R24") (pin "2") (pinfunction "2_2") (pintype "passive"))
      (node (ref "U4") (pin "61") (pinfunction "GD1/CN59/RE1_61") (pintype "bidirectional"))
      (node (ref "U7") (pin "1") (pinfunction "FAULT_1") (pintype "bidirectional"))
    )
    (net (code "11") (name "/FAULT3") (class "Default")
      (node (ref "LED8") (pin "A") (pinfunction "A_A") (pintype "passive"))
      (node (ref "R25") (pin "2") (pinfunction "2_2") (pintype "passive"))
      (node (ref "U4") (pin "62") (pinfunction "GD2/CN60/RE2_62") (pintype "bidirectional"))
      (node (ref "U8") (pin "1") (pinfunction "FAULT_1") (pintype "bidirectional"))
    )
    (net (code "12") (name "/FAULT4") (class "Default")
      (node (ref "LED9") (pin "A") (pinfunction "A_A") (pintype "passive"))
      (node (ref "R26") (pin "2") (pinfunction "2_2") (pintype "passive"))
      (node (ref "U4") (pin "63") (pinfunction "GD3/CN61/RE3_63") (pintype "bidirectional"))
      (node (ref "U9") (pin "1") (pinfunction "FAULT_1") (pintype "bidirectional"))
    )
    (net (code "13") (name "/HOST") (class "Default")
      (node (ref "U4") (pin "40") (pinfunction "OSCO/CLKO/CN22/RC15_40") (pintype "bidirectional"))
    )
    (net (code "14") (name "/IN") (class "Default")
      (node (ref "DRV") (pin "1") (pinfunction "INPUT_1") (pintype "bidirectional"))
      (node (ref "R6") (pin "1") (pinfunction "1_1") (pintype "passive"))
      (node (ref "SW1") (pin "C1") (pinfunction "C1_C1") (pintype "bidirectional"))
      (node (ref "SW1") (pin "C2") (pinfunction "C2_C2") (pintype "bidirectional"))
    )
    (net (code "15") (name "/LEFT") (class "Default")
      (node (ref "C29") (pin "2") (pinfunction "2_2") (pintype "passive"))
      (node (ref "C32") (pin "2") (pinfunction "2_2") (pintype "passive"))
      (node (ref "C35") (pin "2") (pinfunction "2_2") (pintype "passive"))
      (node (ref "C38") (pin "2") (pinfunction "2_2") (pintype "passive"))
      (node (ref "JP6") (pin "1") (pinfunction "1_1") (pintype "passive"))
    )
    (net (code "16") (name "/MCLR") (class "Default")
      (node (ref "PICKIT3") (pin "1") (pinfunction "1_1") (pintype "passive"))
      (node (ref "R18") (pin "2") (pinfunction "2_2") (pintype "passive"))
      (node (ref "R28") (pin "1") (pinfunction "1_1") (pintype "passive"))
    )
    (net (code "17") (name "/NGATE") (class "Default")
      (node (ref "Q1") (pin "4") (pinfunction "G_4") (pintype "bidirectional"))
      (node (ref "U3") (pin "11") (pinfunction "NDRV_11") (pintype "bidirectional"))
    )
    (net (code "18") (name "/OUT-") (class "Default")
      (node (ref "JP9") (pin "P$2") (pinfunction "2_P$2") (pintype "passive"))
      (node (ref "U6") (pin "9") (pinfunction "OUTB_9") (pintype "bidirectional"))
    )
    (net (code "19") (name "/OUT1+") (class "Default")
      (node (ref "JP9") (pin "P$1") (pinfunction "1_P$1") (pintype "passive"))
      (node (ref "U6") (pin "7") (pinfunction "OUTA_7") (pintype "bidirectional"))
    )
    (net (code "20") (name "/OUT2+") (class "Default")
      (node (ref "JP11") (pin "P$1") (pinfunction "1_P$1") (pintype "passive"))
      (node (ref "U7") (pin "7") (pinfunction "OUTA_7") (pintype "bidirectional"))
    )
    (net (code "21") (name "/OUT2-") (class "Default")
      (node (ref "JP11") (pin "P$2") (pinfunction "2_P$2") (pintype "passive"))
      (node (ref "U7") (pin "9") (pinfunction "OUTB_9") (pintype "bidirectional"))
    )
    (net (code "22") (name "/OUT3+") (class "Default")
      (node (ref "JP12") (pin "P$1") (pinfunction "1_P$1") (pintype "passive"))
      (node (ref "U8") (pin "7") (pinfunction "OUTA_7") (pintype "bidirectional"))
    )
    (net (code "23") (name "/OUT3-") (class "Default")
      (node (ref "JP12") (pin "P$2") (pinfunction "2_P$2") (pintype "passive"))
      (node (ref "U8") (pin "9") (pinfunction "OUTB_9") (pintype "bidirectional"))
    )
    (net (code "24") (name "/OUT4+") (class "Default")
      (node (ref "JP13") (pin "P$1") (pinfunction "1_P$1") (pintype "passive"))
      (node (ref "U9") (pin "7") (pinfunction "OUTA_7") (pintype "bidirectional"))
    )
    (net (code "25") (name "/OUT4-") (class "Default")
      (node (ref "JP13") (pin "P$2") (pinfunction "2_P$2") (pintype "passive"))
      (node (ref "U9") (pin "9") (pinfunction "OUTB_9") (pintype "bidirectional"))
    )
    (net (code "26") (name "/PG") (class "Default")
      (node (ref "R3") (pin "2") (pinfunction "2_2") (pintype "passive"))
      (node (ref "U1") (pin "7") (pinfunction "PG_7") (pintype "bidirectional"))
    )
    (net (code "27") (name "/PGATE") (class "Default")
      (node (ref "Q2") (pin "4") (pinfunction "G_4") (pintype "bidirectional"))
      (node (ref "U3") (pin "13") (pinfunction "PDRV_13") (pintype "bidirectional"))
    )
    (net (code "28") (name "/PGEC1") (class "Default")
      (node (ref "PICKIT3") (pin "5") (pinfunction "5_5") (pintype "passive"))
      (node (ref "U4") (pin "15") (pinfunction "PGEC1/AN1/VREF-/RP1/CN3/RB1_15") (pintype "bidirectional"))
    )
    (net (code "29") (name "/PGED1") (class "Default")
      (node (ref "PICKIT3") (pin "4") (pinfunction "4_4") (pintype "passive"))
      (node (ref "U4") (pin "16") (pinfunction "PGED1/AN0/VREF+/RP0/CN2/RB0_16") (pintype "bidirectional"))
    )
    (net (code "30") (name "/PIN3") (class "Default")
      (node (ref "U4") (pin "42") (pinfunction "RTCC/DMLN/RP2/CN53/RD8_42") (pintype "bidirectional"))
    )
    (net (code "31") (name "/PIN6") (class "Default")
      (node (ref "U4") (pin "45") (pinfunction "RP12/GD7/CN56/RD11_45") (pintype "bidirectional"))
    )
    (net (code "32") (name "/PIN7") (class "Default")
      (node (ref "U4") (pin "46") (pinfunction "DMH/RP11/INT0/CN49/RD0_46") (pintype "bidirectional"))
    )
    (net (code "33") (name "/PIN8") (class "Default")
      (node (ref "U4") (pin "47") (pinfunction "SOSCI/C3IND/CN1/RC13_47") (pintype "bidirectional"))
    )
    (net (code "34") (name "/PIN9") (class "Default")
      (node (ref "U4") (pin "48") (pinfunction "SOSCO/SCLKI/T1CK/C3INC/RPI37/CN0/RC14_48") (pintype "bidirectional"))
    )
    (net (code "35") (name "/PIN10") (class "Default")
      (node (ref "U4") (pin "49") (pinfunction "VCPCON/RP24/GD9/VBUSCHG/CN50/RD1_49") (pintype "bidirectional"))
    )
    (net (code "36") (name "/PIN11") (class "Default")
      (node (ref "U4") (pin "50") (pinfunction "DPH/RP23/CN51/RD2_50") (pintype "bidirectional"))
    )
    (net (code "37") (name "/PIN13") (class "Default")
      (node (ref "U4") (pin "52") (pinfunction "RP25/GCLK/CN13/RD4_52") (pintype "bidirectional"))
    )
    (net (code "38") (name "/PIN14") (class "Default")
      (node (ref "U4") (pin "53") (pinfunction "RP20/GPWR/CN14/RD5_53") (pintype "bidirectional"))
    )
    (net (code "39") (name "/PIN15") (class "Default")
      (node (ref "U4") (pin "54") (pinfunction "C3INB/CN15/RD6_54") (pintype "bidirectional"))
    )
    (net (code "40") (name "/PIN16") (class "Default")
      (node (ref "U4") (pin "55") (pinfunction "C3INA/SESSEND/CN16/RD7_55") (pintype "bidirectional"))
    )
    (net (code "41") (name "/PIN17") (class "Default")
      (node (ref "U4") (pin "58") (pinfunction "GD10/VBUSST/VCMPST1/VBUSVLD/CN68/RF0_58") (pintype "bidirectional"))
    )
    (net (code "42") (name "/PIN18") (class "Default")
      (node (ref "U4") (pin "59") (pinfunction "GD11/VCMPST2/SESSVLD/CN69/RF1_59") (pintype "bidirectional"))
    )
    (net (code "43") (name "/PIN23") (class "Default")
      (node (ref "U4") (pin "64") (pinfunction "HSYNC/CN62/RE4_64") (pintype "bidirectional"))
    )
    (net (code "44") (name "/PIN24") (class "Default")
      (node (ref "JP1") (pin "6") (pinfunction "6_6") (pintype "passive"))
      (node (ref "U4") (pin "1") (pinfunction "VSYNC/CN63/RE5_1") (pintype "bidirectional"))
    )
    (net (code "45") (name "/PIN25") (class "Default")
      (node (ref "JP1") (pin "5") (pinfunction "5_5") (pintype "passive"))
      (node (ref "U4") (pin "2") (pinfunction "GD12/SCL3/CN64/RE6_2") (pintype "bidirectional"))
    )
    (net (code "46") (name "/PIN26") (class "Default")
      (node (ref "JP1") (pin "4") (pinfunction "4_4") (pintype "passive"))
      (node (ref "U4") (pin "3") (pinfunction "GD13/SDA3/CN65/RE7_3") (pintype "bidirectional"))
    )
    (net (code "47") (name "/PIN27") (class "Default")
      (node (ref "JP1") (pin "3") (pinfunction "3_3") (pintype "passive"))
      (node (ref "U4") (pin "4") (pinfunction "C1IND/RP21/CN8/RG6_4") (pintype "bidirectional"))
    )
    (net (code "48") (name "/PIN28") (class "Default")
      (node (ref "JP1") (pin "2") (pinfunction "2_2") (pintype "passive"))
      (node (ref "U4") (pin "5") (pinfunction "C1INC/RP26/CN9/RG7_5") (pintype "bidirectional"))
    )
    (net (code "49") (name "/PIN29") (class "Default")
      (node (ref "JP1") (pin "1") (pinfunction "1_1") (pintype "passive"))
      (node (ref "U4") (pin "6") (pinfunction "C2IND/RP19/GD14/CN10/RG8_6") (pintype "bidirectional"))
    )
    (net (code "50") (name "/PIN30") (class "Default")
      (node (ref "U4") (pin "8") (pinfunction "C2INC/RP27/GD15/CN11/RG9_8") (pintype "bidirectional"))
    )
    (net (code "51") (name "/PIN31") (class "Default")
      (node (ref "U4") (pin "11") (pinfunction "PGEC3/AN5/C1INA/VBUSON/RP18/CN7/RB5_11") (pintype "bidirectional"))
    )
    (net (code "52") (name "/PIN32") (class "Default")
      (node (ref "U4") (pin "12") (pinfunction "PGED3/AN4/C1INB/USBOEN/RP28/CN6/RB4_12") (pintype "bidirectional"))
    )
    (net (code "53") (name "/PIN33") (class "Default")
      (node (ref "U4") (pin "13") (pinfunction "AN3/C2INA/VPIO/CN5/RB3_13") (pintype "bidirectional"))
    )
    (net (code "54") (name "/PIN34") (class "Default")
      (node (ref "U4") (pin "14") (pinfunction "AN2/C2INB/VMIO/RP13/CN4/RB2_14") (pintype "bidirectional"))
    )
    (net (code "55") (name "/PIN37") (class "Default")
      (node (ref "JP10") (pin "6") (pinfunction "6_6") (pintype "passive"))
      (node (ref "U4") (pin "17") (pinfunction "PGEC2/AN6/RP6/CN24/RB6_17") (pintype "bidirectional"))
    )
    (net (code "56") (name "/PIN38") (class "Default")
      (node (ref "JP10") (pin "5") (pinfunction "5_5") (pintype "passive"))
      (node (ref "U4") (pin "18") (pinfunction "PGED2/AN7/RP7/RCV/CN25/RB7_18") (pintype "bidirectional"))
    )
    (net (code "57") (name "/PIN39") (class "Default")
      (node (ref "JP10") (pin "4") (pinfunction "4_4") (pintype "passive"))
      (node (ref "U4") (pin "21") (pinfunction "AN8/RP8/CN26/RB8_21") (pintype "bidirectional"))
    )
    (net (code "58") (name "/PIN40") (class "Default")
      (node (ref "JP10") (pin "3") (pinfunction "3_3") (pintype "passive"))
      (node (ref "U4") (pin "22") (pinfunction "AN9/RP9/CN27/RB9_22") (pintype "bidirectional"))
    )
    (net (code "59") (name "/PIN41") (class "Default")
      (node (ref "JP10") (pin "2") (pinfunction "2_2") (pintype "passive"))
      (node (ref "U4") (pin "23") (pinfunction "TMS/CVREF/AN10/CN28/RB10_23") (pintype "bidirectional"))
    )
    (net (code "60") (name "/PIN42") (class "Default")
      (node (ref "JP10") (pin "1") (pinfunction "1_1") (pintype "passive"))
      (node (ref "U4") (pin "24") (pinfunction "TDO/AN11/CN29/RB11_24") (pintype "bidirectional"))
    )
    (net (code "61") (name "/PIN43") (class "Default")
      (node (ref "JP14") (pin "6") (pinfunction "6_6") (pintype "passive"))
      (node (ref "U4") (pin "27") (pinfunction "TCK/AN12/CTEDG2/CN30/RB12_27") (pintype "bidirectional"))
    )
    (net (code "62") (name "/PIN44") (class "Default")
      (node (ref "JP14") (pin "5") (pinfunction "5_5") (pintype "passive"))
      (node (ref "U4") (pin "28") (pinfunction "TDI/AN13/CTEDG1/CN31/RB13_28") (pintype "bidirectional"))
    )
    (net (code "63") (name "/PIN45") (class "Default")
      (node (ref "JP14") (pin "4") (pinfunction "4_4") (pintype "passive"))
      (node (ref "U4") (pin "29") (pinfunction "AN14/CTPLS/RP14/CN32/RB14_29") (pintype "bidirectional"))
    )
    (net (code "64") (name "/PIN46") (class "Default")
      (node (ref "JP14") (pin "3") (pinfunction "3_3") (pintype "passive"))
      (node (ref "U4") (pin "30") (pinfunction "AN15/RP29/REFO/CN12/RB15_30") (pintype "bidirectional"))
    )
    (net (code "65") (name "/PROG") (class "Default")
      (node (ref "R4") (pin "2") (pinfunction "2_2") (pintype "passive"))
      (node (ref "U1") (pin "6") (pinfunction "PROG_6") (pintype "bidirectional"))
    )
    (net (code "66") (name "/PWMOUT") (class "Default")
      (node (ref "JP8") (pin "2") (pinfunction "2_2") (pintype "passive"))
      (node (ref "R27") (pin "1") (pinfunction "1_1") (pintype "passive"))
      (node (ref "U4") (pin "51") (pinfunction "RP22/GEN/CN52/RD3_51") (pintype "bidirectional"))
      (node (ref "U5") (pin "P3") (pinfunction "IN_P3") (pintype "bidirectional"))
    )
    (net (code "67") (name "/RIGHT") (class "Default")
      (node (ref "C28") (pin "2") (pinfunction "2_2") (pintype "passive"))
      (node (ref "C31") (pin "2") (pinfunction "2_2") (pintype "passive"))
      (node (ref "C34") (pin "2") (pinfunction "2_2") (pintype "passive"))
      (node (ref "C37") (pin "2") (pinfunction "2_2") (pintype "passive"))
      (node (ref "JP6") (pin "3") (pinfunction "3_3") (pintype "passive"))
    )
    (net (code "68") (name "/SCL0") (class "Default")
      (node (ref "R19") (pin "2") (pinfunction "2_2") (pintype "passive"))
      (node (ref "U4") (pin "44") (pinfunction "SCL1/RP3/GD6/CN55/RD10_44") (pintype "bidirectional"))
      (node (ref "U6") (pin "2") (pinfunction "SCL_2") (pintype "bidirectional"))
      (node (ref "U7") (pin "2") (pinfunction "SCL_2") (pintype "bidirectional"))
    )
    (net (code "69") (name "/SCL1") (class "Default")
      (node (ref "JP14") (pin "1") (pinfunction "1_1") (pintype "passive"))
      (node (ref "R21") (pin "2") (pinfunction "2_2") (pintype "passive"))
      (node (ref "U4") (pin "32") (pinfunction "SCL2/RP17/GD5/CN18/RF5_32") (pintype "bidirectional"))
      (node (ref "U8") (pin "2") (pinfunction "SCL_2") (pintype "bidirectional"))
      (node (ref "U9") (pin "2") (pinfunction "SCL_2") (pintype "bidirectional"))
    )
    (net (code "70") (name "/SDA0") (class "Default")
      (node (ref "R20") (pin "2") (pinfunction "2_2") (pintype "passive"))
      (node (ref "U4") (pin "43") (pinfunction "DPLN/SDA1/RP4/GD8/CN54/RD9_43") (pintype "bidirectional"))
      (node (ref "U6") (pin "3") (pinfunction "SDA_3") (pintype "bidirectional"))
      (node (ref "U7") (pin "3") (pinfunction "SDA_3") (pintype "bidirectional"))
    )
    (net (code "71") (name "/SDA1") (class "Default")
      (node (ref "JP14") (pin "2") (pinfunction "2_2") (pintype "passive"))
      (node (ref "R22") (pin "2") (pinfunction "2_2") (pintype "passive"))
      (node (ref "U4") (pin "31") (pinfunction "SDA2/RP10/GD4/CN17/RF4_31") (pintype "bidirectional"))
      (node (ref "U8") (pin "3") (pinfunction "SDA_3") (pintype "bidirectional"))
      (node (ref "U9") (pin "3") (pinfunction "SDA_3") (pintype "bidirectional"))
    )
    (net (code "72") (name "/SWITCH+") (class "Default")
      (node (ref "D1") (pin "A1") (pinfunction "A1_A1") (pintype "passive"))
      (node (ref "D1") (pin "A2") (pinfunction "A2_A2") (pintype "passive"))
      (node (ref "L1") (pin "P1") (pinfunction "1_P1") (pintype "bidirectional"))
      (node (ref "Q1") (pin "5") (pinfunction "D1_5") (pintype "bidirectional"))
      (node (ref "Q1") (pin "6") (pinfunction "D2_6") (pintype "bidirectional"))
      (node (ref "Q1") (pin "7") (pinfunction "D3_7") (pintype "bidirectional"))
      (node (ref "Q1") (pin "8") (pinfunction "D4_8") (pintype "bidirectional"))
      (node (ref "Q1") (pin "PAD") (pinfunction "PAD_PAD") (pintype "bidirectional"))
      (node (ref "Q2") (pin "1") (pinfunction "D1_1") (pintype "bidirectional"))
      (node (ref "Q2") (pin "2") (pinfunction "D2_2") (pintype "bidirectional"))
      (node (ref "Q2") (pin "3") (pinfunction "D3_3") (pintype "bidirectional"))
      (node (ref "R7") (pin "2") (pinfunction "2_2") (pintype "passive"))
      (node (ref "R8") (pin "2") (pinfunction "2_2") (pintype "passive"))
      (node (ref "R9") (pin "2") (pinfunction "2_2") (pintype "passive"))
    )
    (net (code "73") (name "/THERMAL") (class "Default")
      (node (ref "R5") (pin "2") (pinfunction "2_2") (pintype "passive"))
      (node (ref "U1") (pin "8") (pinfunction "THERM_8") (pintype "bidirectional"))
    )
    (net (code "74") (name "GND") (class "Default")
      (node (ref "C10") (pin "2") (pinfunction "2_2") (pintype "passive"))
      (node (ref "C11") (pin "2") (pinfunction "2_2") (pintype "passive"))
      (node (ref "C12") (pin "2") (pinfunction "2_2") (pintype "passive"))
      (node (ref "C16") (pin "2") (pinfunction "2_2") (pintype "passive"))
      (node (ref "C17") (pin "2") (pinfunction "2_2") (pintype "passive"))
      (node (ref "C18") (pin "2") (pinfunction "2_2") (pintype "passive"))
      (node (ref "C19") (pin "2") (pinfunction "2_2") (pintype "passive"))
      (node (ref "C20") (pin "2") (pinfunction "2_2") (pintype "passive"))
      (node (ref "C21") (pin "2") (pinfunction "2_2") (pintype "passive"))
      (node (ref "C22") (pin "2") (pinfunction "2_2") (pintype "passive"))
      (node (ref "C23") (pin "2") (pinfunction "2_2") (pintype "passive"))
      (node (ref "C24") (pin "2") (pinfunction "2_2") (pintype "passive"))
      (node (ref "C25") (pin "2") (pinfunction "2_2") (pintype "passive"))
      (node (ref "C26") (pin "2") (pinfunction "2_2") (pintype "passive"))
      (node (ref "C27") (pin "2") (pinfunction "2_2") (pintype "passive"))
      (node (ref "C3") (pin "2") (pinfunction "2_2") (pintype "passive"))
      (node (ref "C30") (pin "2") (pinfunction "2_2") (pintype "passive"))
      (node (ref "C33") (pin "2") (pinfunction "2_2") (pintype "passive"))
      (node (ref "C36") (pin "2") (pinfunction "2_2") (pintype "passive"))
      (node (ref "C39") (pin "2") (pinfunction "2_2") (pintype "passive"))
      (node (ref "C4") (pin "-") (pinfunction "-_-") (pintype "passive"))
      (node (ref "C40") (pin "2") (pinfunction "2_2") (pintype "passive"))
      (node (ref "C41") (pin "2") (pinfunction "2_2") (pintype "passive"))
      (node (ref "C42") (pin "2") (pinfunction "2_2") (pintype "passive"))
      (node (ref "C43") (pin "2") (pinfunction "2_2") (pintype "passive"))
      (node (ref "C44") (pin "2") (pinfunction "2_2") (pintype "passive"))
      (node (ref "C45") (pin "2") (pinfunction "2_2") (pintype "passive"))
      (node (ref "C46") (pin "2") (pinfunction "2_2") (pintype "passive"))
      (node (ref "C47") (pin "2") (pinfunction "2_2") (pintype "passive"))
      (node (ref "C48") (pin "2") (pinfunction "2_2") (pintype "passive"))
      (node (ref "C5") (pin "-") (pinfunction "-_-") (pintype "passive"))
      (node (ref "C6") (pin "2") (pinfunction "2_2") (pintype "passive"))
      (node (ref "C7") (pin "2") (pinfunction "2_2") (pintype "passive"))
      (node (ref "C8") (pin "2") (pinfunction "2_2") (pintype "passive"))
      (node (ref "DRV") (pin "2") (pinfunction "DRAIN_2") (pintype "bidirectional"))
      (node (ref "DRV") (pin "PAD") (pinfunction "TAB_PAD") (pintype "bidirectional"))
      (node (ref "JP5") (pin "1") (pinfunction "1_1") (pintype "passive"))
      (node (ref "JP5") (pin "2") (pinfunction "2_2") (pintype "passive"))
      (node (ref "JP5") (pin "3") (pinfunction "3_3") (pintype "passive"))
      (node (ref "JP6") (pin "2") (pinfunction "2_2") (pintype "passive"))
      (node (ref "JP7") (pin "2A") (pinfunction "2A_2A") (pintype "passive"))
      (node (ref "JP7") (pin "2B") (pinfunction "2B_2B") (pintype "bidirectional"))
      (node (ref "JP8") (pin "1") (pinfunction "1_1") (pintype "passive"))
      (node (ref "LDO") (pin "2") (pinfunction "GND_2") (pintype "input"))
      (node (ref "LDO") (pin "PAD") (pinfunction "PAD_PAD") (pintype "input"))
      (node (ref "LED6") (pin "C") (pinfunction "C_C") (pintype "passive"))
      (node (ref "LED7") (pin "C") (pinfunction "C_C") (pintype "passive"))
      (node (ref "LED8") (pin "C") (pinfunction "C_C") (pintype "passive"))
      (node (ref "LED9") (pin "C") (pinfunction "C_C") (pintype "passive"))
      (node (ref "PICKIT3") (pin "3") (pinfunction "3_3") (pintype "passive"))
      (node (ref "PWR") (pin "1") (pinfunction "GND_1") (pintype "power_in"))
      (node (ref "PWR") (pin "2") (pinfunction "GND_INS_2") (pintype "power_in"))
      (node (ref "Q1") (pin "1") (pinfunction "S1_1") (pintype "bidirectional"))
      (node (ref "Q1") (pin "2") (pinfunction "S2_2") (pintype "bidirectional"))
      (node (ref "Q1") (pin "3") (pinfunction "S3_3") (pintype "bidirectional"))
      (node (ref "Q3") (pin "S") (pinfunction "S_S") (pintype "bidirectional"))
      (node (ref "R12") (pin "1") (pinfunction "1_1") (pintype "passive"))
      (node (ref "R14") (pin "2") (pinfunction "2_2") (pintype "passive"))
      (node (ref "R17") (pin "2") (pinfunction "2_2") (pintype "passive"))
      (node (ref "R27") (pin "2") (pinfunction "2_2") (pintype "passive"))
      (node (ref "U$1") (pin "4") (pinfunction "GND_4") (pintype "bidirectional"))
      (node (ref "U$1") (pin "S1") (pinfunction "S1_S1") (pintype "bidirectional"))
      (node (ref "U$1") (pin "S2") (pinfunction "S2_S2") (pintype "bidirectional"))
      (node (ref "U$4") (pin "S2") (pinfunction "S2_S2") (pintype "bidirectional"))
      (node (ref "U3") (pin "1") (pinfunction "SYNC/SD_1") (pintype "bidirectional"))
      (node (ref "U3") (pin "12") (pinfunction "GND_12") (pintype "bidirectional"))
      (node (ref "U3") (pin "2") (pinfunction "CCS_2") (pintype "bidirectional"))
      (node (ref "U3") (pin "5") (pinfunction "BUCK_5") (pintype "bidirectional"))
      (node (ref "U4") (pin "20") (pinfunction "AVSS_20") (pintype "power_in"))
      (node (ref "U4") (pin "25") (pinfunction "VSS_25") (pintype "power_in"))
      (node (ref "U4") (pin "33") (pinfunction "RP16/USBID/CN71/RF3_33") (pintype "bidirectional"))
      (node (ref "U4") (pin "41") (pinfunction "VSS_41") (pintype "power_in"))
      (node (ref "U4") (pin "9") (pinfunction "VSS_9") (pintype "power_in"))
      (node (ref "U5") (pin "P1") (pinfunction "NC_P1") (pintype "bidirectional"))
      (node (ref "U5") (pin "P4") (pinfunction "GND_P4") (pintype "bidirectional"))
      (node (ref "U6") (pin "5") (pinfunction "GND_5") (pintype "bidirectional"))
      (node (ref "U6") (pin "6") (pinfunction "ADR_6") (pintype "bidirectional"))
      (node (ref "U6") (pin "8") (pinfunction "PGND_8") (pintype "bidirectional"))
      (node (ref "U6") (pin "PAD") (pinfunction "PAD_PAD") (pintype "bidirectional"))
      (node (ref "U7") (pin "5") (pinfunction "GND_5") (pintype "bidirectional"))
      (node (ref "U7") (pin "8") (pinfunction "PGND_8") (pintype "bidirectional"))
      (node (ref "U7") (pin "PAD") (pinfunction "PAD_PAD") (pintype "bidirectional"))
      (node (ref "U8") (pin "5") (pinfunction "GND_5") (pintype "bidirectional"))
      (node (ref "U8") (pin "6") (pinfunction "ADR_6") (pintype "bidirectional"))
      (node (ref "U8") (pin "8") (pinfunction "PGND_8") (pintype "bidirectional"))
      (node (ref "U8") (pin "PAD") (pinfunction "PAD_PAD") (pintype "bidirectional"))
      (node (ref "U9") (pin "5") (pinfunction "GND_5") (pintype "bidirectional"))
      (node (ref "U9") (pin "8") (pinfunction "PGND_8") (pintype "bidirectional"))
      (node (ref "U9") (pin "PAD") (pinfunction "PAD_PAD") (pintype "bidirectional"))
    )
    (net (code "75") (name "Net-(C3-Pad1)") (class "Default")
      (node (ref "C3") (pin "1") (pinfunction "1_1") (pintype "passive"))
      (node (ref "R8") (pin "1") (pinfunction "1_1") (pintype "passive"))
    )
    (net (code "76") (name "Net-(C9-Pad1)") (class "Default")
      (node (ref "C9") (pin "1") (pinfunction "1_1") (pintype "passive"))
      (node (ref "R9") (pin "1") (pinfunction "1_1") (pintype "passive"))
    )
    (net (code "77") (name "Net-(C13-Pad2)") (class "Default")
      (node (ref "C13") (pin "2") (pinfunction "2_2") (pintype "passive"))
      (node (ref "R11") (pin "1") (pinfunction "1_1") (pintype "passive"))
    )
    (net (code "78") (name "Net-(C14-Pad2)") (class "Default")
      (node (ref "C14") (pin "2") (pinfunction "2_2") (pintype "passive"))
      (node (ref "R13") (pin "2") (pinfunction "2_2") (pintype "passive"))
    )
    (net (code "79") (name "Net-(C22-Pad1)") (class "Default")
      (node (ref "C22") (pin "1") (pinfunction "1_1") (pintype "passive"))
      (node (ref "C24") (pin "1") (pinfunction "1_1") (pintype "passive"))
      (node (ref "C25") (pin "1") (pinfunction "1_1") (pintype "passive"))
      (node (ref "JP7") (pin "1A") (pinfunction "1A_1A") (pintype "passive"))
      (node (ref "JP7") (pin "1B") (pinfunction "1B_1B") (pintype "bidirectional"))
      (node (ref "U$4") (pin "S1") (pinfunction "S1_S1") (pintype "bidirectional"))
    )
    (net (code "80") (name "Net-(LED1-PadC)") (class "Default")
      (node (ref "LED1") (pin "C") (pinfunction "C_C") (pintype "passive"))
      (node (ref "R1") (pin "1") (pinfunction "1_1") (pintype "passive"))
    )
    (net (code "81") (name "Net-(LED2-PadC)") (class "Default")
      (node (ref "LED2") (pin "C") (pinfunction "C_C") (pintype "passive"))
      (node (ref "R2") (pin "1") (pinfunction "1_1") (pintype "passive"))
    )
    (net (code "82") (name "Net-(LED3-PadC)") (class "Default")
      (node (ref "LED3") (pin "C") (pinfunction "C_C") (pintype "passive"))
      (node (ref "R3") (pin "1") (pinfunction "1_1") (pintype "passive"))
    )
    (net (code "83") (name "Net-(LED4-PadA)") (class "Default")
      (node (ref "LED4") (pin "A") (pinfunction "A_A") (pintype "passive"))
      (node (ref "R16") (pin "2") (pinfunction "2_2") (pintype "passive"))
    )
    (net (code "84") (name "Net-(LED5-PadC)") (class "Default")
      (node (ref "LED5") (pin "C") (pinfunction "C_C") (pintype "passive"))
      (node (ref "R17") (pin "1") (pinfunction "1_1") (pintype "passive"))
    )
    (net (code "85") (name "Net-(Q3-PadD)") (class "Default")
      (node (ref "Q3") (pin "D") (pinfunction "D_D") (pintype "bidirectional"))
      (node (ref "U$4") (pin "P2") (pinfunction "P2_P2") (pintype "bidirectional"))
    )
    (net (code "86") (name "Net-(Q3-PadG)") (class "Default")
      (node (ref "Q3") (pin "G") (pinfunction "G_G") (pintype "bidirectional"))
      (node (ref "R15") (pin "1") (pinfunction "1_1") (pintype "passive"))
    )
    (net (code "87") (name "Net-(U3-COMP)") (class "Default")
      (node (ref "C14") (pin "1") (pinfunction "1_1") (pintype "passive"))
      (node (ref "C15") (pin "1") (pinfunction "1_1") (pintype "passive"))
      (node (ref "U3") (pin "7") (pinfunction "COMP_7") (pintype "bidirectional"))
    )
    (net (code "88") (name "Net-(U3-FB)") (class "Default")
      (node (ref "C13") (pin "1") (pinfunction "1_1") (pintype "passive"))
      (node (ref "C15") (pin "2") (pinfunction "2_2") (pintype "passive"))
      (node (ref "R10") (pin "1") (pinfunction "1_1") (pintype "passive"))
      (node (ref "R12") (pin "2") (pinfunction "2_2") (pintype "passive"))
      (node (ref "R13") (pin "1") (pinfunction "1_1") (pintype "passive"))
      (node (ref "U3") (pin "8") (pinfunction "FB_8") (pintype "bidirectional"))
    )
    (net (code "89") (name "Net-(U3-RT)") (class "Default")
      (node (ref "R14") (pin "1") (pinfunction "1_1") (pintype "passive"))
      (node (ref "U3") (pin "3") (pinfunction "RT_3") (pintype "bidirectional"))
    )
    (net (code "90") (name "Net-(U3-SWN)") (class "Default")
      (node (ref "R7") (pin "1") (pinfunction "1_1") (pintype "passive"))
      (node (ref "U3") (pin "15") (pinfunction "SWP_15") (pintype "bidirectional"))
      (node (ref "U3") (pin "16") (pinfunction "SWN_16") (pintype "bidirectional"))
    )
    (net (code "91") (name "Net-(U4-VCAP)") (class "Default")
      (node (ref "C20") (pin "1") (pinfunction "1_1") (pintype "passive"))
      (node (ref "U4") (pin "56") (pinfunction "VCAP_56") (pintype "power_in"))
    )
    (net (code "92") (name "Net-(U4-~{MCLR})") (class "Default")
      (node (ref "R28") (pin "2") (pinfunction "2_2") (pintype "passive"))
      (node (ref "U4") (pin "7") (pinfunction "~{MCLR}_7") (pintype "input"))
    )
    (net (code "93") (name "Net-(U5-OUT)") (class "Default")
      (node (ref "R15") (pin "2") (pinfunction "2_2") (pintype "passive"))
      (node (ref "U5") (pin "P5") (pinfunction "OUT_P5") (pintype "bidirectional"))
    )
    (net (code "94") (name "Net-(U6-BIAS)") (class "Default")
      (node (ref "C27") (pin "1") (pinfunction "1_1") (pintype "passive"))
      (node (ref "U6") (pin "13") (pinfunction "BIAS_13") (pintype "bidirectional"))
    )
    (net (code "95") (name "Net-(U6-IN1)") (class "Default")
      (node (ref "C29") (pin "1") (pinfunction "1_1") (pintype "passive"))
      (node (ref "U6") (pin "12") (pinfunction "IN1_12") (pintype "bidirectional"))
    )
    (net (code "96") (name "Net-(U6-IN2)") (class "Default")
      (node (ref "C28") (pin "1") (pinfunction "1_1") (pintype "passive"))
      (node (ref "U6") (pin "11") (pinfunction "IN2_11") (pintype "bidirectional"))
    )
    (net (code "97") (name "Net-(U7-BIAS)") (class "Default")
      (node (ref "C30") (pin "1") (pinfunction "1_1") (pintype "passive"))
      (node (ref "U7") (pin "13") (pinfunction "BIAS_13") (pintype "bidirectional"))
    )
    (net (code "98") (name "Net-(U7-IN1)") (class "Default")
      (node (ref "C32") (pin "1") (pinfunction "1_1") (pintype "passive"))
      (node (ref "U7") (pin "12") (pinfunction "IN1_12") (pintype "bidirectional"))
    )
    (net (code "99") (name "Net-(U7-IN2)") (class "Default")
      (node (ref "C31") (pin "1") (pinfunction "1_1") (pintype "passive"))
      (node (ref "U7") (pin "11") (pinfunction "IN2_11") (pintype "bidirectional"))
    )
    (net (code "100") (name "Net-(U8-BIAS)") (class "Default")
      (node (ref "C33") (pin "1") (pinfunction "1_1") (pintype "passive"))
      (node (ref "U8") (pin "13") (pinfunction "BIAS_13") (pintype "bidirectional"))
    )
    (net (code "101") (name "Net-(U8-IN1)") (class "Default")
      (node (ref "C35") (pin "1") (pinfunction "1_1") (pintype "passive"))
      (node (ref "U8") (pin "12") (pinfunction "IN1_12") (pintype "bidirectional"))
    )
    (net (code "102") (name "Net-(U8-IN2)") (class "Default")
      (node (ref "C34") (pin "1") (pinfunction "1_1") (pintype "passive"))
      (node (ref "U8") (pin "11") (pinfunction "IN2_11") (pintype "bidirectional"))
    )
    (net (code "103") (name "Net-(U9-BIAS)") (class "Default")
      (node (ref "C36") (pin "1") (pinfunction "1_1") (pintype "passive"))
      (node (ref "U9") (pin "13") (pinfunction "BIAS_13") (pintype "bidirectional"))
    )
    (net (code "104") (name "Net-(U9-IN1)") (class "Default")
      (node (ref "C38") (pin "1") (pinfunction "1_1") (pintype "passive"))
      (node (ref "U9") (pin "12") (pinfunction "IN1_12") (pintype "bidirectional"))
    )
    (net (code "105") (name "Net-(U9-IN2)") (class "Default")
      (node (ref "C37") (pin "1") (pinfunction "1_1") (pintype "passive"))
      (node (ref "U9") (pin "11") (pinfunction "IN2_11") (pintype "bidirectional"))
    )
    (net (code "106") (name "V+") (class "Default")
      (node (ref "C10") (pin "1") (pinfunction "1_1") (pintype "passive"))
      (node (ref "C2") (pin "1") (pinfunction "1_1") (pintype "passive"))
      (node (ref "C4") (pin "+") (pinfunction "+_+") (pintype "passive"))
      (node (ref "C6") (pin "1") (pinfunction "1_1") (pintype "passive"))
      (node (ref "J1") (pin "P2") (pinfunction "P2_P2") (pintype "bidirectional"))
      (node (ref "L1") (pin "P2") (pinfunction "2_P2") (pintype "bidirectional"))
      (node (ref "SW1") (pin "A1") (pinfunction "A1_A1") (pintype "bidirectional"))
      (node (ref "SW1") (pin "A2") (pinfunction "A2_A2") (pintype "bidirectional"))
      (node (ref "U1") (pin "10") (pinfunction "VBAT1_10") (pintype "bidirectional"))
      (node (ref "U1") (pin "9") (pinfunction "VBAT2_9") (pintype "bidirectional"))
      (node (ref "U3") (pin "4") (pinfunction "CCM_4") (pintype "bidirectional"))
      (node (ref "U3") (pin "6") (pinfunction "~{PFM}_6") (pintype "bidirectional"))
      (node (ref "U3") (pin "9") (pinfunction "VIN_9") (pintype "bidirectional"))
    )
    (net (code "107") (name "V-") (class "Default")
      (node (ref "C1") (pin "2") (pinfunction "2_2") (pintype "passive"))
      (node (ref "C2") (pin "2") (pinfunction "2_2") (pintype "passive"))
      (node (ref "DRV") (pin "3") (pinfunction "SOURCE_3") (pintype "bidirectional"))
      (node (ref "J1") (pin "P1") (pinfunction "P1_P1") (pintype "bidirectional"))
      (node (ref "J2") (pin "5") (pinfunction "GND_5") (pintype "bidirectional"))
      (node (ref "JP2") (pin "2") (pinfunction "2_2") (pintype "passive"))
      (node (ref "R4") (pin "1") (pinfunction "1_1") (pintype "passive"))
      (node (ref "R5") (pin "1") (pinfunction "1_1") (pintype "passive"))
      (node (ref "R6") (pin "2") (pinfunction "2_2") (pintype "passive"))
      (node (ref "SW1") (pin "B1") (pinfunction "B1_B1") (pintype "bidirectional"))
      (node (ref "SW1") (pin "B2") (pinfunction "B2_B2") (pintype "bidirectional"))
      (node (ref "U1") (pin "5") (pinfunction "GND_5") (pintype "bidirectional"))
    )
    (net (code "108") (name "VCC") (class "Default")
      (node (ref "C11") (pin "1") (pinfunction "1_1") (pintype "passive"))
      (node (ref "C12") (pin "1") (pinfunction "1_1") (pintype "passive"))
      (node (ref "C26") (pin "1") (pinfunction "1_1") (pintype "passive"))
      (node (ref "C40") (pin "1") (pinfunction "1_1") (pintype "passive"))
      (node (ref "C41") (pin "1") (pinfunction "1_1") (pintype "passive"))
      (node (ref "C42") (pin "1") (pinfunction "1_1") (pintype "passive"))
      (node (ref "C43") (pin "1") (pinfunction "1_1") (pintype "passive"))
      (node (ref "C44") (pin "1") (pinfunction "1_1") (pintype "passive"))
      (node (ref "C45") (pin "1") (pinfunction "1_1") (pintype "passive"))
      (node (ref "C46") (pin "1") (pinfunction "1_1") (pintype "passive"))
      (node (ref "C47") (pin "1") (pinfunction "1_1") (pintype "passive"))
      (node (ref "C5") (pin "+") (pinfunction "+_+") (pintype "passive"))
      (node (ref "C7") (pin "1") (pinfunction "1_1") (pintype "passive"))
      (node (ref "C8") (pin "1") (pinfunction "1_1") (pintype "passive"))
      (node (ref "C9") (pin "2") (pinfunction "2_2") (pintype "passive"))
      (node (ref "D1") (pin "C") (pinfunction "C_C") (pintype "passive"))
      (node (ref "JP4") (pin "1") (pinfunction "1_1") (pintype "passive"))
      (node (ref "JP4") (pin "2") (pinfunction "2_2") (pintype "passive"))
      (node (ref "JP4") (pin "3") (pinfunction "3_3") (pintype "passive"))
      (node (ref "JP8") (pin "3") (pinfunction "3_3") (pintype "passive"))
      (node (ref "PWR") (pin "3") (pinfunction "PWR_1_3") (pintype "power_in"))
      (node (ref "PWR") (pin "4") (pinfunction "PWR_2_4") (pintype "power_in"))
      (node (ref "Q2") (pin "5") (pinfunction "S1_5") (pintype "bidirectional"))
      (node (ref "Q2") (pin "6") (pinfunction "S2_6") (pintype "bidirectional"))
      (node (ref "Q2") (pin "7") (pinfunction "S3_7") (pintype "bidirectional"))
      (node (ref "Q2") (pin "8") (pinfunction "S4_8") (pintype "bidirectional"))
      (node (ref "Q2") (pin "PAD") (pinfunction "PAD_PAD") (pintype "bidirectional"))
      (node (ref "R10") (pin "2") (pinfunction "2_2") (pintype "passive"))
      (node (ref "R11") (pin "2") (pinfunction "2_2") (pintype "passive"))
      (node (ref "R23") (pin "1") (pinfunction "1_1") (pintype "passive"))
      (node (ref "R24") (pin "1") (pinfunction "1_1") (pintype "passive"))
      (node (ref "R25") (pin "1") (pinfunction "1_1") (pintype "passive"))
      (node (ref "R26") (pin "1") (pinfunction "1_1") (pintype "passive"))
      (node (ref "U$4") (pin "P1") (pinfunction "P1_P1") (pintype "bidirectional"))
      (node (ref "U3") (pin "10") (pinfunction "VOUT_10") (pintype "bidirectional"))
      (node (ref "U3") (pin "14") (pinfunction "VP_14") (pintype "bidirectional"))
      (node (ref "U5") (pin "P2") (pinfunction "VDD_P2") (pintype "bidirectional"))
      (node (ref "U6") (pin "10") (pinfunction "PVDD_10") (pintype "bidirectional"))
      (node (ref "U6") (pin "14") (pinfunction "VDD_14") (pintype "bidirectional"))
      (node (ref "U7") (pin "10") (pinfunction "PVDD_10") (pintype "bidirectional"))
      (node (ref "U7") (pin "14") (pinfunction "VDD_14") (pintype "bidirectional"))
      (node (ref "U8") (pin "10") (pinfunction "PVDD_10") (pintype "bidirectional"))
      (node (ref "U8") (pin "14") (pinfunction "VDD_14") (pintype "bidirectional"))
      (node (ref "U9") (pin "10") (pinfunction "PVDD_10") (pintype "bidirectional"))
      (node (ref "U9") (pin "14") (pinfunction "VDD_14") (pintype "bidirectional"))
    )
    (net (code "109") (name "unconnected-(J2-D+-Pad3)") (class "Default")
      (node (ref "J2") (pin "3") (pinfunction "D+_3") (pintype "bidirectional"))
    )
    (net (code "110") (name "unconnected-(J2-D--Pad2)") (class "Default")
      (node (ref "J2") (pin "2") (pinfunction "D-_2") (pintype "bidirectional"))
    )
    (net (code "111") (name "unconnected-(J2-ID-Pad4)") (class "Default")
      (node (ref "J2") (pin "4") (pinfunction "ID_4") (pintype "bidirectional"))
    )
  )
)
